# SDA381V8_B0.net
KiCad netlist of a schematic drawn in EAGLE
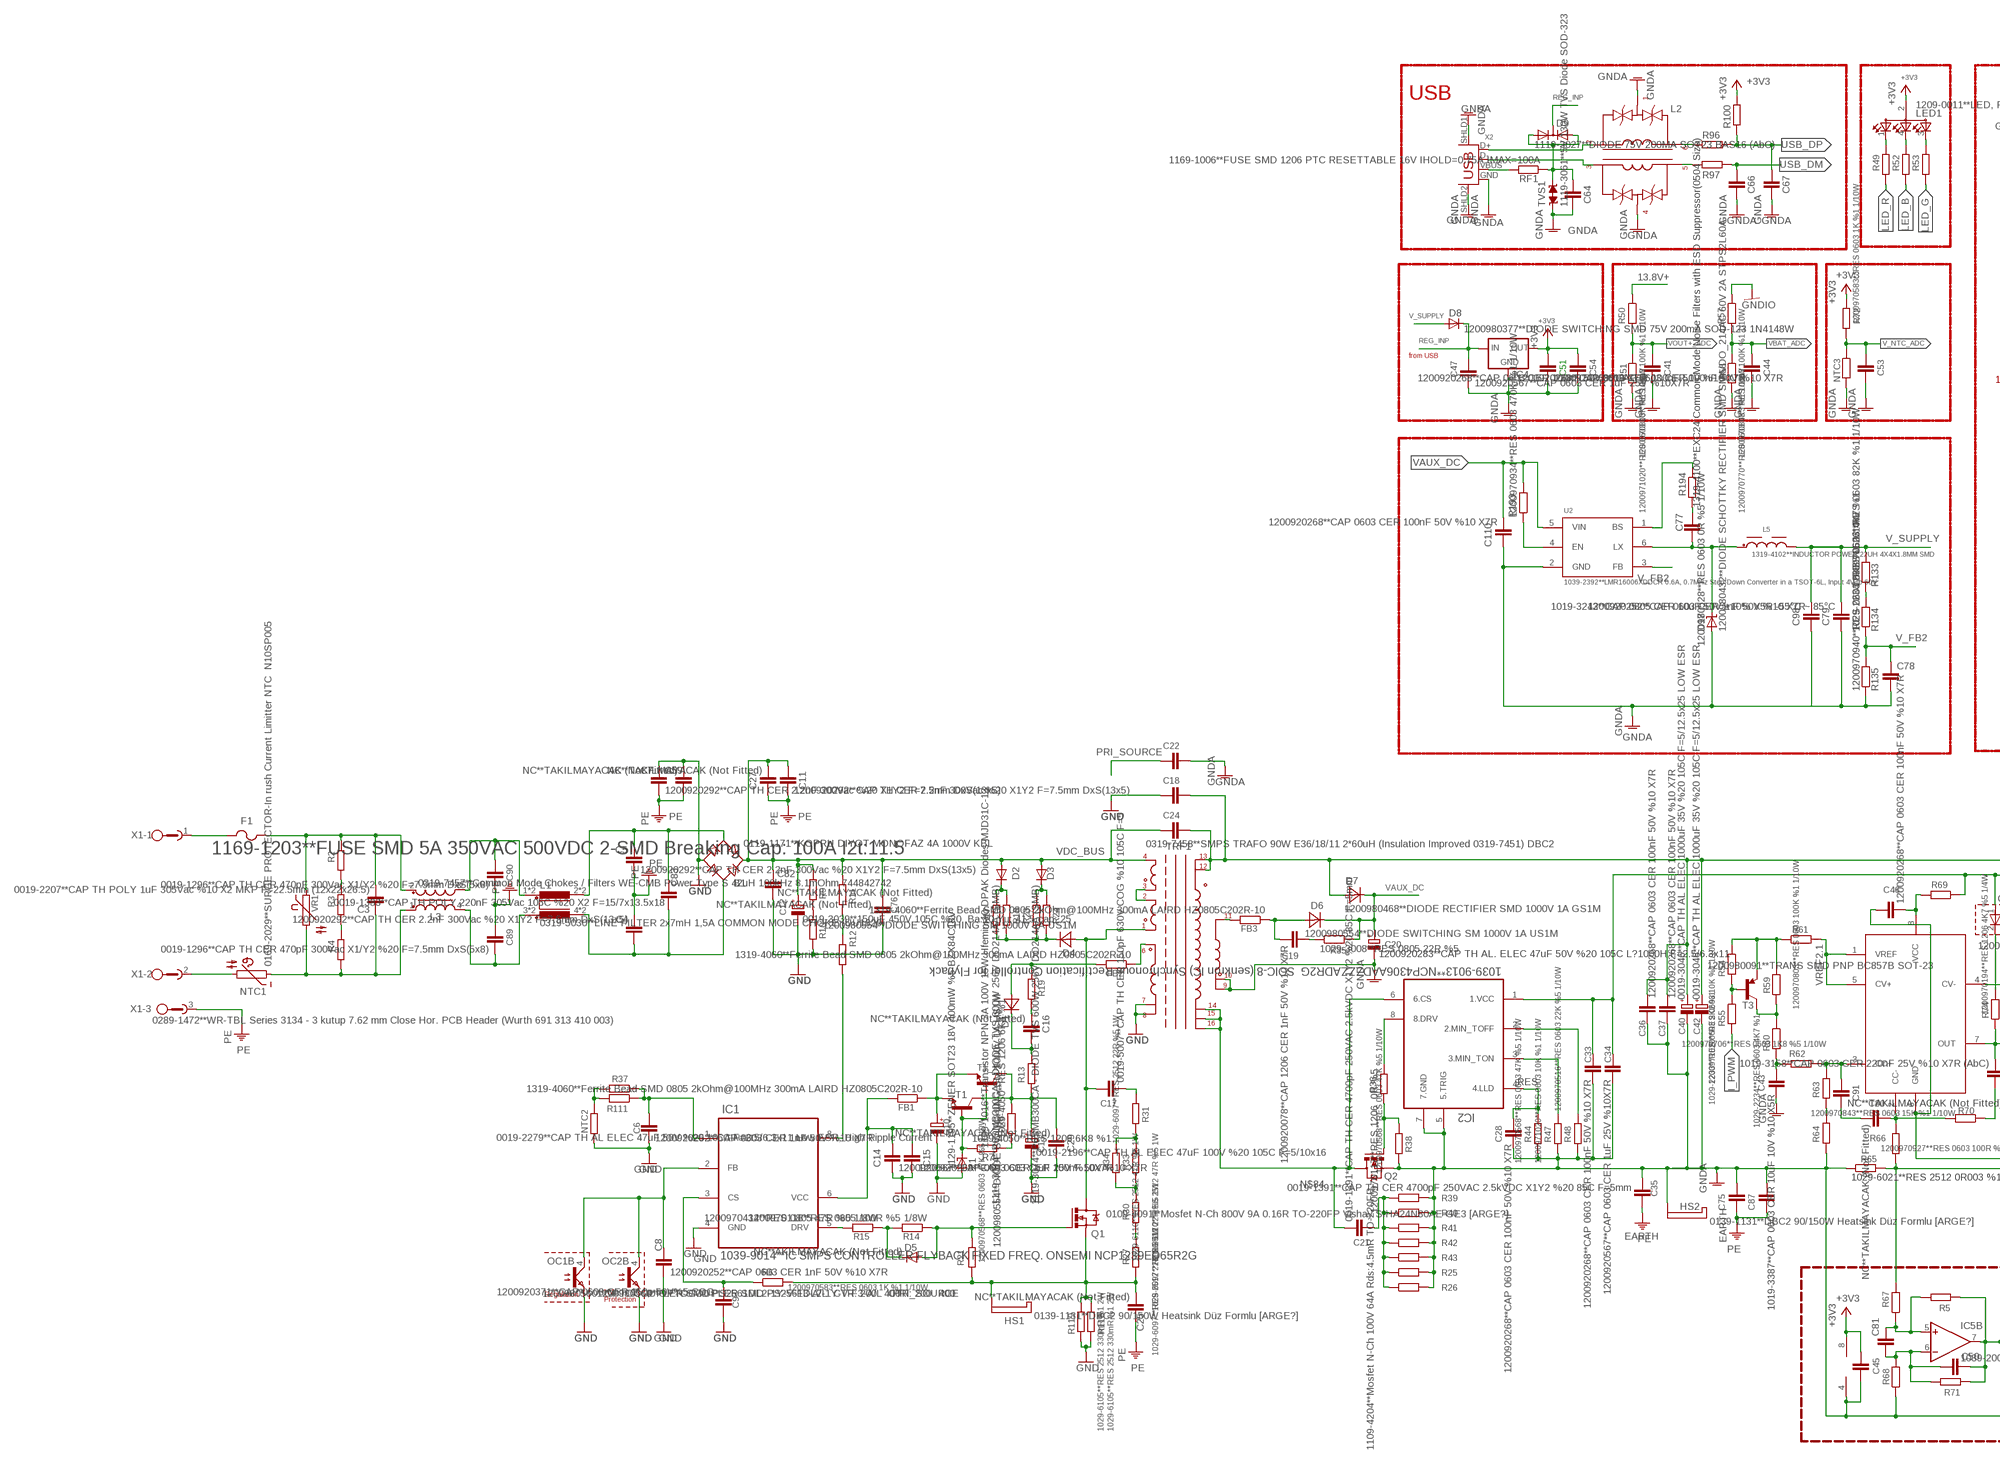
[diagram p0: schematic, sheet 1, part 1 of 2]
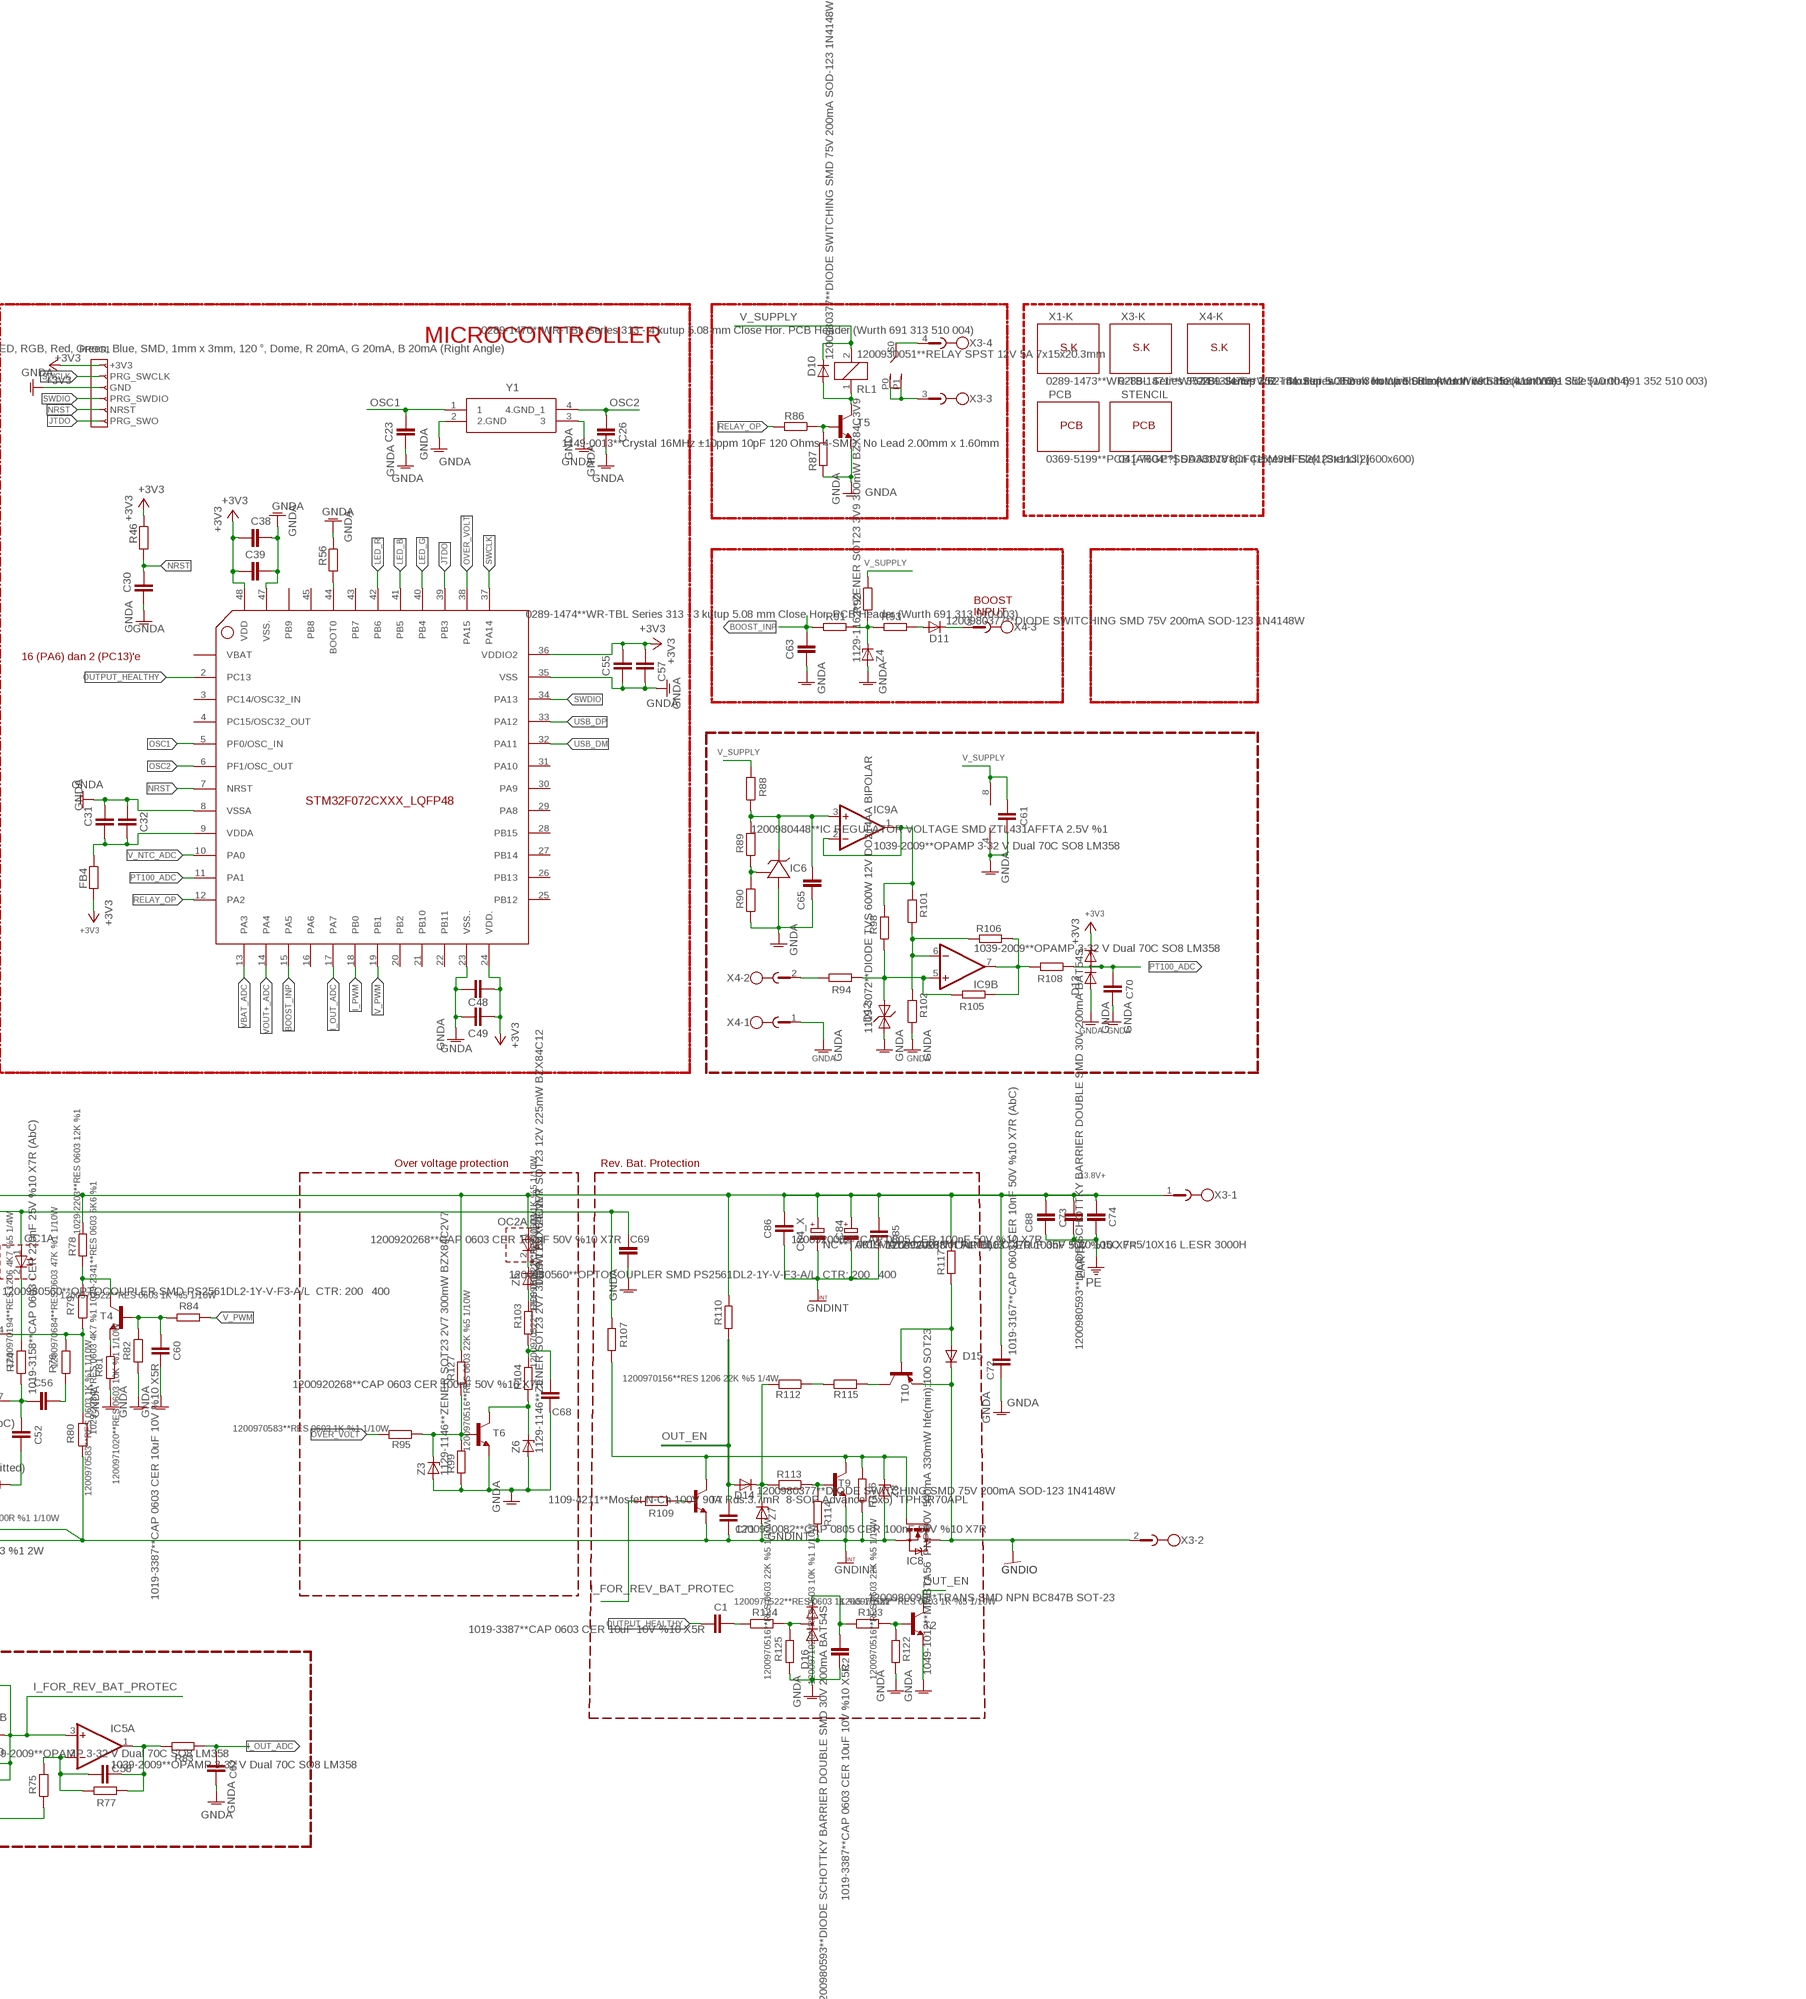
[diagram p1: schematic, sheet 1, part 2 of 2]

(export (version "E")
  (design (tool "Eeschema 10.0.6"))
  (components
    (comp (ref "B1")
      (value "0119-1171**KOPRU DIYOT MONOFAZ 4A 1000V KBL")
      (footprint "eagle-import:DıODE_BRIDGE_8A_DIK")
      (libsource (lib "eagle-import") (part "DıODE_BRIDGE_8A_DIK"))
    )
    (comp (ref "C1")
      (value "1019-3387**CAP 0603 CER 10uF 10V %10 X5R")
      (footprint "eagle-import:C0603_ENKO")
      (libsource (lib "eagle-import") (part "C-EUC0603E"))
    )
    (comp (ref "C2")
      (value "1019-3387**CAP 0603 CER 10uF 10V %10 X5R")
      (footprint "eagle-import:C0603_ENKO")
      (libsource (lib "eagle-import") (part "C-EUC0603E"))
    )
    (comp (ref "C3")
      (value "0019-2207**CAP TH POLY 1uF 305Vac %10 X2 MKP F=22.5mm (12x22x26.5)")
      (footprint "eagle-import:C275-113X316_&_C150-072X183_&_C225-113X268")
      (libsource (lib "eagle-import") (part "C275-113X316_&_C150-072X183_&_C225-113X268"))
    )
    (comp (ref "C4")
      (value "1200920292**CAP TH CER 2.2nF 300Vac %20 X1Y2 F=7.5mm DxS(13x5)")
      (footprint "eagle-import:C075-042X103")
      (libsource (lib "eagle-import") (part "C-EU075-042X103"))
    )
    (comp (ref "C5")
      (value "1200920292**CAP TH CER 2.2nF 300Vac %20 X1Y2 F=7.5mm DxS(13x5)")
      (footprint "eagle-import:C075-042X103")
      (libsource (lib "eagle-import") (part "C-EU075-042X103"))
    )
    (comp (ref "C6")
      (value "1200920252**CAP 0603 CER 1nF 50V %10 X7R")
      (footprint "eagle-import:C0603_ENKO")
      (libsource (lib "eagle-import") (part "C-EUC0603E"))
    )
    (comp (ref "C7")
      (value "1200920292**CAP TH CER 2.2nF 300Vac %20 X1Y2 F=7.5mm DxS(13x5)")
      (footprint "eagle-import:C075-042X103")
      (libsource (lib "eagle-import") (part "C-EU075-042X103"))
    )
    (comp (ref "C8")
      (value "1200920252**CAP 0603 CER 1nF 50V %10 X7R")
      (footprint "eagle-import:C0603_ENKO")
      (libsource (lib "eagle-import") (part "C-EUC0603E"))
    )
    (comp (ref "C9")
      (value "1200920371**CAP 0603 CER 150p 50V%5 COG")
      (footprint "eagle-import:C0603_ENKO")
      (libsource (lib "eagle-import") (part "C-EUC0603E"))
    )
    (comp (ref "C10")
      (value "0019-2279**CAP TH AL ELEC 47uF 50V %20 105C F=2.5/6.3x11 Low ESR, High Ripple Current")
      (footprint "eagle-import:E2,5-7")
      (libsource (lib "eagle-import") (part "CPOL-EUE2.5-7"))
    )
    (comp (ref "C11")
      (value "1200920292**CAP TH CER 2.2nF 300Vac %20 X1Y2 F=7.5mm DxS(13x5)")
      (footprint "eagle-import:C075-042X103")
      (libsource (lib "eagle-import") (part "C-EU075-042X103"))
    )
    (comp (ref "C12")
      (value "0019-3039**150uF 450V 105C %20 Ba:10 Yu: 41,5 çap: 25")
      (footprint "eagle-import:EB25D")
      (libsource (lib "eagle-import") (part "CPOL-EUE10-25"))
    )
    (comp (ref "C13")
      (value "0019-2196**CAP TH AL ELEC 47uF 100V %20 105C F=5/10x16")
      (footprint "eagle-import:E5-10,5")
      (libsource (lib "eagle-import") (part "CPOL-EUE5-10.5"))
    )
    (comp (ref "C14")
      (value "1200920567**CAP 0603 CER 1uF 25V %10X7R")
      (footprint "eagle-import:C0603_ENKO")
      (libsource (lib "eagle-import") (part "C-EUC0603E"))
    )
    (comp (ref "C15")
      (value "1200920268**CAP 0603 CER 100nF 50V %10 X7R")
      (footprint "eagle-import:C0603_ENKO")
      (libsource (lib "eagle-import") (part "C-EUC0603E"))
    )
    (comp (ref "C16")
      (value "NC**TAKILMAYACAK (Not Fitted)")
      (footprint "eagle-import:C1206_ENKO")
      (libsource (lib "eagle-import") (part "C-EUC1206E"))
    )
    (comp (ref "C17")
      (value "0019-5007**CAP TH CER 150pF 630V COG %10 105C F=5")
      (footprint "eagle-import:C075-32X103_C050-035X75")
      (libsource (lib "eagle-import") (part "C075-32X103/C050-035X75"))
    )
    (comp (ref "C18")
      (value "0019-1298**CAP TH CER 1nF 500Vac X1/Y1 %20 F=10mm DxS(5x9)")
      (footprint "eagle-import:C075-32X103_DEIF")
      (libsource (lib "eagle-import") (part "C075-32X103_DEIF"))
    )
    (comp (ref "C19")
      (value "1200920078**CAP 1206 CER 1nF 50V %10 X7R")
      (footprint "eagle-import:C1206_ENKO")
      (libsource (lib "eagle-import") (part "C-EUC1206E"))
    )
    (comp (ref "C20")
      (value "1200920283**CAP TH AL. ELEC 47uF 50V %20 105C L?1000H F=2.5/6.3x11")
      (footprint "eagle-import:E2,5-7")
      (libsource (lib "eagle-import") (part "CPOL-EUE2.5-7"))
    )
    (comp (ref "C21")
      (value "0019-1391**CAP TH CER 4700pF 250VAC 2.5kVDC X1Y2 %20 85C F=5mm")
      (footprint "eagle-import:C075-32X103_C050-035X75")
      (libsource (lib "eagle-import") (part "C075-32X103/C050-035X75"))
    )
    (comp (ref "C22")
      (value "0019-1298**CAP TH CER 1nF 500Vac X1/Y1 %20 F=10mm DxS(5x9)")
      (footprint "eagle-import:C075-32X103_DEIF")
      (libsource (lib "eagle-import") (part "C075-32X103_DEIF"))
    )
    (comp (ref "C23")
      (value "1019-3352**CAP 0603 CER 22pF 50V %5 NPO")
      (footprint "eagle-import:C0603_ENKO")
      (libsource (lib "eagle-import") (part "C-EUC0603E"))
    )
    (comp (ref "C24")
      (value "0019-1299**CAP TH CER 2.2nF 500Vac X1/Y1 %20 F=10mm DxS(5x12)")
      (footprint "eagle-import:C075-32X103_DEIF")
      (libsource (lib "eagle-import") (part "C075-32X103_DEIF"))
    )
    (comp (ref "C25")
      (value "NC**TAKILMAYACAK (Not Fitted)")
      (footprint "eagle-import:C50-035X75")
      (libsource (lib "eagle-import") (part "C50-035X75"))
    )
    (comp (ref "C26")
      (value "1019-3352**CAP 0603 CER 22pF 50V %5 NPO")
      (footprint "eagle-import:C0603_ENKO")
      (libsource (lib "eagle-import") (part "C-EUC0603E"))
    )
    (comp (ref "C27")
      (value "NC**TAKILMAYACAK (Not Fitted)")
      (footprint "eagle-import:C50-035X75")
      (libsource (lib "eagle-import") (part "C50-035X75"))
    )
    (comp (ref "C28")
      (value "1200920268**CAP 0603 CER 100nF 50V %10 X7R")
      (footprint "eagle-import:C0603_ENKO")
      (libsource (lib "eagle-import") (part "C-EUC0603E"))
    )
    (comp (ref "C29")
      (value "NC**TAKILMAYACAK (Not Fitted)")
      (footprint "eagle-import:C1206_ENKO")
      (libsource (lib "eagle-import") (part "C-EUC1206E"))
    )
    (comp (ref "C30")
      (value "1200920268**CAP 0603 CER 100nF 50V %10 X7R")
      (footprint "eagle-import:C0603_ENKO")
      (libsource (lib "eagle-import") (part "C-EUC0603E"))
    )
    (comp (ref "C31")
      (value "1200920268**CAP 0603 CER 100nF 50V %10 X7R")
      (footprint "eagle-import:C0603_ENKO")
      (libsource (lib "eagle-import") (part "C-EUC0603E"))
    )
    (comp (ref "C32")
      (value "1019-3167**CAP 0603 CER 10nF 50V %10 X7R (AbC)")
      (footprint "eagle-import:C0603_ENKO")
      (libsource (lib "eagle-import") (part "C-EUC0603E"))
    )
    (comp (ref "C33")
      (value "1200920268**CAP 0603 CER 100nF 50V %10 X7R")
      (footprint "eagle-import:C0603_ENKO")
      (libsource (lib "eagle-import") (part "C-EUC0603E"))
    )
    (comp (ref "C34")
      (value "1200920567**CAP 0603 CER 1uF 25V %10X7R")
      (footprint "eagle-import:C0603_ENKO")
      (libsource (lib "eagle-import") (part "C-EUC0603E"))
    )
    (comp (ref "C35")
      (value "0019-1391**CAP TH CER 4700pF 250VAC 2.5kVDC X1Y2 %20 85C F=5mm")
      (footprint "eagle-import:C050-045X075")
      (libsource (lib "eagle-import") (part "C-EU050-045X075"))
    )
    (comp (ref "C36")
      (value "1200920268**CAP 0603 CER 100nF 50V %10 X7R")
      (footprint "eagle-import:C0603_ENKO")
      (libsource (lib "eagle-import") (part "C-EUC0603E"))
    )
    (comp (ref "C37")
      (value "1200920268**CAP 0603 CER 100nF 50V %10 X7R")
      (footprint "eagle-import:C0603_ENKO")
      (libsource (lib "eagle-import") (part "C-EUC0603E"))
    )
    (comp (ref "C38")
      (value "1200920268**CAP 0603 CER 100nF 50V %10 X7R")
      (footprint "eagle-import:C0603_ENKO")
      (libsource (lib "eagle-import") (part "C-EUC0603E"))
    )
    (comp (ref "C39")
      (value "1019-3167**CAP 0603 CER 10nF 50V %10 X7R (AbC)")
      (footprint "eagle-import:C0603_ENKO")
      (libsource (lib "eagle-import") (part "C-EUC0603E"))
    )
    (comp (ref "C40")
      (value "0019-3046**CAP TH AL ELEC 1000uF 35V %20 105C F=5/12.5x25 LOW ESR")
      (footprint "eagle-import:E5-13_E7,5-16")
      (libsource (lib "eagle-import") (part "E5-13/E7,5-16"))
    )
    (comp (ref "C41")
      (value "1200920268**CAP 0603 CER 100nF 50V %10 X7R")
      (footprint "eagle-import:C0603_ENKO")
      (libsource (lib "eagle-import") (part "C-EUC0603E"))
    )
    (comp (ref "C42")
      (value "0019-3046**CAP TH AL ELEC 1000uF 35V %20 105C F=5/12.5x25 LOW ESR")
      (footprint "eagle-import:E5-13")
      (libsource (lib "eagle-import") (part "CPOL-EUE5-13"))
    )
    (comp (ref "C43")
      (value "1019-3387**CAP 0603 CER 10uF 10V %10 X5R")
      (footprint "eagle-import:C0603_ENKO")
      (libsource (lib "eagle-import") (part "C-EUC0603E"))
    )
    (comp (ref "C44")
      (value "1200920268**CAP 0603 CER 100nF 50V %10 X7R")
      (footprint "eagle-import:C0603_ENKO")
      (libsource (lib "eagle-import") (part "C-EUC0603E"))
    )
    (comp (ref "C45")
      (value "1200920268**CAP 0603 CER 100nF 50V %10 X7R")
      (footprint "eagle-import:C0603_ENKO")
      (libsource (lib "eagle-import") (part "C-EUC0603E"))
    )
    (comp (ref "C46")
      (value "1200920268**CAP 0603 CER 100nF 50V %10 X7R")
      (footprint "eagle-import:C0603_ENKO")
      (libsource (lib "eagle-import") (part "C-EUC0603E"))
    )
    (comp (ref "C47")
      (value "1200920567**CAP 0603 CER 1uF 25V %10X7R")
      (footprint "eagle-import:C0603_ENKO")
      (libsource (lib "eagle-import") (part "C-EUC0603E"))
    )
    (comp (ref "C48")
      (value "1019-3167**CAP 0603 CER 10nF 50V %10 X7R (AbC)")
      (footprint "eagle-import:C0603_ENKO")
      (libsource (lib "eagle-import") (part "C-EUC0603E"))
    )
    (comp (ref "C49")
      (value "1200920268**CAP 0603 CER 100nF 50V %10 X7R")
      (footprint "eagle-import:C0603_ENKO")
      (libsource (lib "eagle-import") (part "C-EUC0603E"))
    )
    (comp (ref "C50")
      (value "NC**TAKILMAYACAK (Not Fitted)")
      (footprint "eagle-import:C0603_ENKO")
      (libsource (lib "eagle-import") (part "C-EUC0603E"))
    )
    (comp (ref "C51")
      (value "1200920268**CAP 0603 CER 100nF 50V %10 X7R")
      (footprint "eagle-import:C0603_ENKO")
      (libsource (lib "eagle-import") (part "C-EUC0603E"))
    )
    (comp (ref "C52")
      (value "1019-3158**CAP 0603 CER 220nF 25V %10 X7R (AbC)")
      (footprint "eagle-import:C0603_ENKO")
      (libsource (lib "eagle-import") (part "C-EUC0603E"))
    )
    (comp (ref "C53")
      (value "1200920268**CAP 0603 CER 100nF 50V %10 X7R")
      (footprint "eagle-import:C0603_ENKO")
      (libsource (lib "eagle-import") (part "C-EUC0603E"))
    )
    (comp (ref "C54")
      (value "1019-3301**CAP 0805 47uF 6.3V %20 X5R")
      (footprint "eagle-import:C0805_ENKO")
      (libsource (lib "eagle-import") (part "C-EUC0805E"))
    )
    (comp (ref "C55")
      (value "1019-3167**CAP 0603 CER 10nF 50V %10 X7R (AbC)")
      (footprint "eagle-import:C0603_ENKO")
      (libsource (lib "eagle-import") (part "C-EUC0603E"))
    )
    (comp (ref "C56")
      (value "1019-3158**CAP 0603 CER 220nF 25V %10 X7R (AbC)")
      (footprint "eagle-import:C0603_ENKO")
      (libsource (lib "eagle-import") (part "C-EUC0603E"))
    )
    (comp (ref "C57")
      (value "1200920268**CAP 0603 CER 100nF 50V %10 X7R")
      (footprint "eagle-import:C0603_ENKO")
      (libsource (lib "eagle-import") (part "C-EUC0603E"))
    )
    (comp (ref "C58")
      (value "1200920371**CAP 0603 CER 150p 50V%5 COG")
      (footprint "eagle-import:C0603_ENKO")
      (libsource (lib "eagle-import") (part "C-EUC0603E"))
    )
    (comp (ref "C59")
      (value "NC**TAKILMAYACAK (Not Fitted)")
      (footprint "eagle-import:C50-035X75")
      (libsource (lib "eagle-import") (part "C50-035X75"))
    )
    (comp (ref "C60")
      (value "1019-3387**CAP 0603 CER 10uF 10V %10 X5R")
      (footprint "eagle-import:C0603_ENKO")
      (libsource (lib "eagle-import") (part "C-EUC0603E"))
    )
    (comp (ref "C61")
      (value "1200920268**CAP 0603 CER 100nF 50V %10 X7R")
      (footprint "eagle-import:C0603_ENKO")
      (libsource (lib "eagle-import") (part "C-EUC0603E"))
    )
    (comp (ref "C62")
      (value "1200920268**CAP 0603 CER 100nF 50V %10 X7R")
      (footprint "eagle-import:C0603_ENKO")
      (libsource (lib "eagle-import") (part "C-EUC0603E"))
    )
    (comp (ref "C63")
      (value "1019-3167**CAP 0603 CER 10nF 50V %10 X7R (AbC)")
      (footprint "eagle-import:C0603_ENKO")
      (libsource (lib "eagle-import") (part "C-EUC0603E"))
    )
    (comp (ref "C64")
      (value "1200920268**CAP 0603 CER 100nF 50V %10 X7R")
      (footprint "eagle-import:C0603_ENKO")
      (libsource (lib "eagle-import") (part "C-EUC0603E"))
    )
    (comp (ref "C65")
      (value "1200920268**CAP 0603 CER 100nF 50V %10 X7R")
      (footprint "eagle-import:C0603_ENKO")
      (libsource (lib "eagle-import") (part "C-EUC0603E"))
    )
    (comp (ref "C66")
      (value "1019-3381**CAP 0603 CER 33pf 50V %5 NPO(COG)")
      (footprint "eagle-import:C0603_ENKO")
      (libsource (lib "eagle-import") (part "C-EUC0603E"))
    )
    (comp (ref "C67")
      (value "1019-3381**CAP 0603 CER 33pf 50V %5 NPO(COG)")
      (footprint "eagle-import:C0603_ENKO")
      (libsource (lib "eagle-import") (part "C-EUC0603E"))
    )
    (comp (ref "C68")
      (value "1200920268**CAP 0603 CER 100nF 50V %10 X7R")
      (footprint "eagle-import:C0603_ENKO")
      (libsource (lib "eagle-import") (part "C-EUC0603E"))
    )
    (comp (ref "C69")
      (value "1200920268**CAP 0603 CER 100nF 50V %10 X7R")
      (footprint "eagle-import:C0603_ENKO")
      (libsource (lib "eagle-import") (part "C-EUC0603E"))
    )
    (comp (ref "C70")
      (value "1200920268**CAP 0603 CER 100nF 50V %10 X7R")
      (footprint "eagle-import:C0603_ENKO")
      (libsource (lib "eagle-import") (part "C-EUC0603E"))
    )
    (comp (ref "C71")
      (value "1200920082**CAP 0805 CER 100nF 50V %10 X7R")
      (footprint "eagle-import:C0805_ENKO")
      (libsource (lib "eagle-import") (part "C-EUC0805E"))
    )
    (comp (ref "C72")
      (value "1019-3167**CAP 0603 CER 10nF 50V %10 X7R (AbC)")
      (footprint "eagle-import:C0603_ENKO")
      (libsource (lib "eagle-import") (part "C-EUC0603E"))
    )
    (comp (ref "C73")
      (value "0019-1391**CAP TH CER 4700pF 250VAC 2.5kVDC X1Y2 %20 85C F=5mm")
      (footprint "eagle-import:C050-035X075")
      (libsource (lib "eagle-import") (part "C-EU050-035X075"))
    )
    (comp (ref "C74")
      (value "0019-1391**CAP TH CER 4700pF 250VAC 2.5kVDC X1Y2 %20 85C F=5mm")
      (footprint "eagle-import:C075-32X103_DEIF")
      (libsource (lib "eagle-import") (part "C075-32X103_DEIF"))
    )
    (comp (ref "C75")
      (value "0019-1391**CAP TH CER 4700pF 250VAC 2.5kVDC X1Y2 %20 85C F=5mm")
      (footprint "eagle-import:C075-32X103_DEIF")
      (libsource (lib "eagle-import") (part "C075-32X103_DEIF"))
    )
    (comp (ref "C76")
      (value "NC**TAKILMAYACAK (Not Fitted)")
      (footprint "eagle-import:C065-052X106")
      (libsource (lib "eagle-import") (part "C065-052X106"))
    )
    (comp (ref "C77")
      (value "1200920268**CAP 0603 CER 100nF 50V %10 X7R")
      (footprint "eagle-import:C0603_ENKO")
      (libsource (lib "eagle-import") (part "C-EUC0603E"))
    )
    (comp (ref "C78")
      (value "1019-3352**CAP 0603 CER 22pF 50V %5 NPO")
      (footprint "eagle-import:C0603_ENKO")
      (libsource (lib "eagle-import") (part "C-EUC0603E"))
    )
    (comp (ref "C79")
      (value "1019-3243**CAP 0805 CER 10uF 50V ±10% X5R -55°C ~ 85°C")
      (footprint "eagle-import:C0805_ENKO")
      (libsource (lib "eagle-import") (part "C-EUC0805E"))
    )
    (comp (ref "C80")
      (value "NC**TAKILMAYACAK (Not Fitted)")
      (footprint "eagle-import:C0603_ENKO")
      (libsource (lib "eagle-import") (part "C-EUC0603E"))
    )
    (comp (ref "C81")
      (value "NC**TAKILMAYACAK (Not Fitted)")
      (footprint "eagle-import:C0603_ENKO")
      (libsource (lib "eagle-import") (part "C-EUC0603E"))
    )
    (comp (ref "C82")
      (value "NC**TAKILMAYACAK (Not Fitted)")
      (footprint "eagle-import:C150-091X182")
      (libsource (lib "eagle-import") (part "C-EU150-091X182"))
    )
    (comp (ref "C83")
      (value "0019-1383**CAP TH POLY 220nF 305Vac 105C %20 X2 F=15/7x13.5x18")
      (footprint "eagle-import:C150-091X182_C225-108X268")
      (libsource (lib "eagle-import") (part "C150-091X182_C225-108X268"))
    )
    (comp (ref "C84")
      (value "0019-7012**CAP TH AL. ELEC 470uF 35V %20 105C F=5/10X16 L.ESR 3000H")
      (footprint "eagle-import:E5-10,5")
      (libsource (lib "eagle-import") (part "CPOL-EUE5-10.5"))
    )
    (comp (ref "C84_X")
      (value "NC**TAKILMAYACAK (Not Fitted)")
      (footprint "eagle-import:E2,5-7")
      (libsource (lib "eagle-import") (part "CPOL-EUE2.5-7"))
    )
    (comp (ref "C85")
      (value "1200920268**CAP 0603 CER 100nF 50V %10 X7R")
      (footprint "eagle-import:C0603_ENKO")
      (libsource (lib "eagle-import") (part "C-EUC0603E"))
    )
    (comp (ref "C86")
      (value "1200920082**CAP 0805 CER 100nF 50V %10 X7R")
      (footprint "eagle-import:C0805_ENKO")
      (libsource (lib "eagle-import") (part "C-EUC0805E"))
    )
    (comp (ref "C87")
      (value "0019-3044**CAP TH CER 1nF 400VAC X1 %20 85C F=5 veya F=7.5 D=6.5")
      (footprint "eagle-import:C075-32X103_DEIF")
      (libsource (lib "eagle-import") (part "C075-32X103_DEIF"))
    )
    (comp (ref "C88")
      (value "0019-3044**CAP TH CER 1nF 400VAC X1 %20 85C F=5 veya F=7.5 D=6.5")
      (footprint "eagle-import:C075-32X103_DEIF")
      (libsource (lib "eagle-import") (part "C075-32X103_DEIF"))
    )
    (comp (ref "C89")
      (value "0019-1296**CAP TH CER 470pF 300Vac X1/Y2 %20 F=7.5mm DxS(5x8)")
      (footprint "eagle-import:C075-32X103_C050-035X75")
      (libsource (lib "eagle-import") (part "C075-32X103/C050-035X75"))
    )
    (comp (ref "C90")
      (value "0019-1296**CAP TH CER 470pF 300Vac X1/Y2 %20 F=7.5mm DxS(5x8)")
      (footprint "eagle-import:C075-32X103_C050-035X75")
      (libsource (lib "eagle-import") (part "C075-32X103/C050-035X75"))
    )
    (comp (ref "C91")
      (value "NC**TAKILMAYACAK (Not Fitted)")
      (footprint "eagle-import:C0603_ENKO")
      (libsource (lib "eagle-import") (part "C-EUC0603E"))
    )
    (comp (ref "C98")
      (value "1200920252**CAP 0603 CER 1nF 50V %10 X7R")
      (footprint "eagle-import:C0603_ENKO")
      (libsource (lib "eagle-import") (part "C-EUC0603E"))
    )
    (comp (ref "C110")
      (value "1200920268**CAP 0603 CER 100nF 50V %10 X7R")
      (footprint "eagle-import:C0603_ENKO")
      (libsource (lib "eagle-import") (part "C-EUC0603E"))
    )
    (comp (ref "D1")
      (value "1200980554**DIODE SWITCHING SM 1000V 1A US1M")
      (footprint "eagle-import:M7_DC_DIYOT")
      (libsource (lib "eagle-import") (part "M7_DC_DIYOT"))
    )
    (comp (ref "D2")
      (value "1119-3074**P6SMB300CA - DIODE TVS 600W 256V DO214AA (SMB)")
      (footprint "eagle-import:SMB")
      (libsource (lib "eagle-import") (part "DIODE-SMB"))
    )
    (comp (ref "D3")
      (value "1119-3074**P6SMB300CA - DIODE TVS 600W 256V DO214AA (SMB)")
      (footprint "eagle-import:SMB")
      (libsource (lib "eagle-import") (part "DIODE-SMB"))
    )
    (comp (ref "D4")
      (value "1200980554**DIODE SWITCHING SM 1000V 1A US1M")
      (footprint "eagle-import:M7_DC_DIYOT")
      (libsource (lib "eagle-import") (part "M7_DC_DIYOT"))
    )
    (comp (ref "D5")
      (value "NC**AKILMAYACAK (Not Fitted)")
      (footprint "eagle-import:SOD123")
      (libsource (lib "eagle-import") (part "DIODE-SOD123"))
    )
    (comp (ref "D6")
      (value "1200980554**DIODE SWITCHING SM 1000V 1A US1M")
      (footprint "eagle-import:M7_DC_DIYOT")
      (libsource (lib "eagle-import") (part "M7_DC_DIYOT"))
    )
    (comp (ref "D7")
      (value "1200980468**DIODE RECTIFIER SMD 1000V 1A GS1M")
      (footprint "eagle-import:M7_DC_DIYOT")
      (libsource (lib "eagle-import") (part "M7_DC_DIYOT"))
    )
    (comp (ref "D8")
      (value "1200980377**DIODE SWITCHING SMD 75V 200mA SOD-123 1N4148W")
      (footprint "eagle-import:SOD123")
      (libsource (lib "eagle-import") (part "DIODE-SOD123"))
    )
    (comp (ref "D9")
      (value "1119-3027**DIODE 75V 200MA SOT23 BAS16 (AbC)")
      (footprint "eagle-import:SOT23")
      (libsource (lib "eagle-import") (part "DIODE-2AC|CASOT23"))
    )
    (comp (ref "D10")
      (value "1200980377**DIODE SWITCHING SMD 75V 200mA SOD-123 1N4148W")
      (footprint "eagle-import:SOD123")
      (libsource (lib "eagle-import") (part "DIODE-SOD123"))
    )
    (comp (ref "D11")
      (value "1200980377**DIODE SWITCHING SMD 75V 200mA SOD-123 1N4148W")
      (footprint "eagle-import:SOD123")
      (libsource (lib "eagle-import") (part "DIODE-SOD123"))
    )
    (comp (ref "D12")
      (value "1119-3072**DIODE TVS 600W 12V DO214AA BIPOLAR")
      (footprint "eagle-import:TRANSIL_SMB")
      (libsource (lib "eagle-import") (part "TRANSIL_SMB"))
    )
    (comp (ref "D13")
      (value "1200980593**DIODE SCHOTTKY BARRIER DOUBLE SMD 30V 200mA BAT54S")
      (footprint "eagle-import:SOT23")
      (libsource (lib "eagle-import") (part "BAV199"))
    )
    (comp (ref "D14")
      (value "1200980377**DIODE SWITCHING SMD 75V 200mA SOD-123 1N4148W")
      (footprint "eagle-import:SOD123")
      (libsource (lib "eagle-import") (part "DIODE-SOD123"))
    )
    (comp (ref "D15")
      (value "1200980377**DIODE SWITCHING SMD 75V 200mA SOD-123 1N4148W")
      (footprint "eagle-import:SOD123")
      (libsource (lib "eagle-import") (part "DIODE-SOD123"))
    )
    (comp (ref "D16")
      (value "1200980593**DIODE SCHOTTKY BARRIER DOUBLE SMD 30V 200mA BAT54S")
      (footprint "eagle-import:SOT23")
      (libsource (lib "eagle-import") (part "BAV199"))
    )
    (comp (ref "D18")
      (value "1200980432**DIODE SCHOTTKY RECTIFIER SMD SMA/DO_214AC 60V 2A STPS2L60A")
      (footprint "eagle-import:SMA")
      (libsource (lib "eagle-import") (part "SD-SMA"))
    )
    (comp (ref "F1")
      (value "1169-1203**FUSE SMD 5A 350VAC 500VDC 2-SMD Breaking Cap: 100A I2t:11.5")
      (footprint "eagle-import:FUSE_1350HV_EAT")
      (fields
        (field (name "MANUFACTURER_PART_NUMBER") "TR-1350HV5-R")
        (field (name "COPYRIGHT") "Copyright (C) 2025 Ultra Librarian. All rights reserved.")
      )
      (libsource (lib "eagle-import") (part "TR-1350HV5-RFUSE_1350HV_EAT"))
    )
    (comp (ref "FB1")
      (value "1319-4060**Ferrite Bead SMD 0805 2kOhm@100MHz 300mA LAIRD HZ0805C202R-10")
      (footprint "eagle-import:R0805_ENKO")
      (libsource (lib "eagle-import") (part "R-EU_R0805E"))
    )
    (comp (ref "FB2")
      (value "1319-4060**Ferrite Bead SMD 0805 2kOhm@100MHz 300mA LAIRD HZ0805C202R-10")
      (footprint "eagle-import:R0805_ENKO")
      (libsource (lib "eagle-import") (part "R-EU_R0805E"))
    )
    (comp (ref "FB3")
      (value "1319-4060**Ferrite Bead SMD 0805 2kOhm@100MHz 300mA LAIRD HZ0805C202R-10")
      (footprint "eagle-import:R0805_ENKO")
      (libsource (lib "eagle-import") (part "R-EU_R0805E"))
    )
    (comp (ref "FB4")
      (value "1319-4060**Ferrite Bead SMD 0805 2kOhm@100MHz 300mA LAIRD HZ0805C202R-10")
      (footprint "eagle-import:R0805_ENKO")
      (libsource (lib "eagle-import") (part "R-EU_R0805E"))
    )
    (comp (ref "HS1")
      (value "0139-1131**DBC2 90/150W Heatsink Düz Formlu [ARGE?]")
      (footprint "eagle-import:DEIF_SOGUTUCU_2")
      (libsource (lib "eagle-import") (part "DEIF_SOGUTUCU_2"))
    )
    (comp (ref "HS2")
      (value "0139-1131**DBC2 90/150W Heatsink Düz Formlu [ARGE?]")
      (footprint "eagle-import:DEIF_SOGUTUCU_2")
      (libsource (lib "eagle-import") (part "DEIF_SOGUTUCU_2"))
    )
    (comp (ref "IC1")
      (value "1039-9014**IC SMPS CONTROLLER FLYBACK FIXED FREQ. ONSEMI NCP1239ED65R2G")
      (footprint "eagle-import:NCP1239_SMPS_IC")
      (libsource (lib "eagle-import") (part "NCP1239_SMPS_IC"))
    )
    (comp (ref "IC2")
      (value "1039-9013**NCP4306AADZZZADR2G SOIC-8 (senkron IC) Synchronous Rectification Controller for Flyback")
      (footprint "eagle-import:NCP4306")
      (libsource (lib "eagle-import") (part "NCP4306"))
    )
    (comp (ref "IC3")
      (value "1039-2224**TSM1011ID SO-8 Constant Voltage and Constant Current Controller")
      (footprint "eagle-import:SO-8")
      (libsource (lib "eagle-import") (part "TSM1011"))
    )
    (comp (ref "IC4")
      (value "1039-3003**Voltage Regulator SOT-89 3.3V Diodes AP2204RA-3.3TRG1")
      (footprint "eagle-import:SOT89")
      (libsource (lib "eagle-import") (part "S-812XSGUP"))
    )
    (comp (ref "IC5")
      (value "1039-2009**OPAMP 3-32 V Dual 70C SO8 LM358")
      (footprint "eagle-import:SO08")
      (libsource (lib "eagle-import") (part "LM358D"))
    )
    (comp (ref "IC6")
      (value "1200980448**IC REGULATOR VOLTAGE SMD ZTL431AFFTA 2.5V %1")
      (footprint "eagle-import:TL431_SOT23F")
      (libsource (lib "eagle-import") (part "TL431_SOT23F"))
    )
    (comp (ref "IC8")
      (value "1109-4211**Mosfet N-Ch 100V 90A Rds:3.7mR 8-SOP Advance (5x5) TPH3R70APL")
      (footprint "eagle-import:TPH6R30ANL")
      (libsource (lib "eagle-import") (part "TPH6R30ANL"))
    )
    (comp (ref "IC9")
      (value "1039-2009**OPAMP 3-32 V Dual 70C SO8 LM358")
      (footprint "eagle-import:SO08")
      (libsource (lib "eagle-import") (part "LM358D"))
    )
    (comp (ref "L1")
      (value "0319-5030**LINE FILTER 2x7mH 1,5A COMMON MODE CHOKE (UU1620)")
      (footprint "eagle-import:UU1620_&_FWCMET24V")
      (libsource (lib "eagle-import") (part "UU1620_&_FWCMET24V"))
    )
    (comp (ref "L2")
      (value "1319-4100**EXC24 Common Mode Noise Filters with ESD Suppressor(0504 Size)")
      (footprint "eagle-import:EXC24CS_COMMON_MODE")
      (libsource (lib "eagle-import") (part "EXC24CS_COMMON_MODE"))
    )
    (comp (ref "L3")
      (value "0319-7457**Common Mode Chokes / Filters WE-CMB Power Type S 42uH 100kHz 8.1mOhm 744842742")
      (footprint "eagle-import:WE-CMB_NIZN_S")
      (libsource (lib "eagle-import") (part "WE-CMB_NIZN_S_744842742"))
    )
    (comp (ref "L5")
      (value "1319-4102**INDUCTOR POWER 22UH 4X4X1.8MM SMD")
      (footprint "eagle-import:INDUCTOR-NR4018")
      (libsource (lib "eagle-import") (part "INDUCTOR-NR4018"))
    )
    (comp (ref "LED1")
      (value "1209-0011**LED, RGB, Red, Green, Blue, SMD, 1mm x 3mm, 120 °, Dome, R 20mA, G 20mA, B 20mA (Right Angle)")
      (footprint "eagle-import:KPFA-3010RGBC-11")
      (libsource (lib "eagle-import") (part "KPFA-3010RGBC-11"))
    )
    (comp (ref "NTC1")
      (value "0169-2029**SURGE PROTECTOR-In rush Current Limitter NTC N10SP005")
      (footprint "eagle-import:NTC_15R_2A_&_N15SP005-5")
      (libsource (lib "eagle-import") (part "NTC_15R_2A_&_N15SP005-5"))
    )
    (comp (ref "NTC2")
      (value "1200970116**RES 0805 0R %5")
      (footprint "eagle-import:R0805_ENKO")
      (libsource (lib "eagle-import") (part "R-EU_R0805E"))
    )
    (comp (ref "NTC3")
      (value "1169-1001**TSM2A103F3951RZ THINKING 0805 10K NTC 125C")
      (footprint "eagle-import:R0805_ENKO")
      (libsource (lib "eagle-import") (part "R-EU_R0805E"))
    )
    (comp (ref "OC1")
      (value "1200980560**OPTOCOUPLER SMD PS2561DL2-1Y-V-F3-A/L  CTR: 200˜400")
      (footprint "eagle-import:PS2561DL2-1_OPTO1")
      (libsource (lib "eagle-import") (part "PS2561DL2-1_OPTO1"))
    )
    (comp (ref "OC2")
      (value "1200980560**OPTOCOUPLER SMD PS2561DL2-1Y-V-F3-A/L  CTR: 200˜400")
      (footprint "eagle-import:PS2561DL2-1_OPTO1")
      (libsource (lib "eagle-import") (part "PS2561DL2-1_OPTO1"))
    )
    (comp (ref "PCB")
      (value "0369-5199**PCB [ARGE?] SDA381V8CF416M3HFS2(123x113.2)")
      (footprint "eagle-import:PCB")
      (libsource (lib "eagle-import") (part "PCB"))
    )
    (comp (ref "PROG1")
      (value "NC**TAKILMAYACAK (Not Fitted)")
      (footprint "eagle-import:PROG_6PIN")
      (libsource (lib "eagle-import") (part "PROG_6PIN"))
    )
    (comp (ref "Q1")
      (value "0109-4091**Mosfet N-Ch 800V 9A 0.16R TO-220FP Vishay SIHA24N80AE-GE3 [ARGE?]")
      (footprint "eagle-import:TO220BV")
      (libsource (lib "eagle-import") (part "STP5NA50"))
    )
    (comp (ref "Q2")
      (value "1109-4204**Mosfet N-Ch 100V 64A Rds:4.5mR TO-220FP")
      (footprint "eagle-import:TO220BV")
      (libsource (lib "eagle-import") (part "STP5NA50"))
    )
    (comp (ref "R2")
      (value "1200970587**RES 1206 470K %5 1/4W")
      (footprint "eagle-import:R1206_ENKO")
      (libsource (lib "eagle-import") (part "R-EU_R1206E"))
    )
    (comp (ref "R3")
      (value "1200970587**RES 1206 470K %5 1/4W")
      (footprint "eagle-import:R1206_ENKO")
      (libsource (lib "eagle-import") (part "R-EU_R1206E"))
    )
    (comp (ref "R4")
      (value "1200970587**RES 1206 470K %5 1/4W")
      (footprint "eagle-import:R1206_ENKO")
      (libsource (lib "eagle-import") (part "R-EU_R1206E"))
    )
    (comp (ref "R5")
      (value "NC**TAKILMAYACAK")
      (footprint "eagle-import:R0603_ENKO")
      (libsource (lib "eagle-import") (part "R-EU_R0603E"))
    )
    (comp (ref "R6")
      (value "1200970583**RES 0603 1K %1 1/10W")
      (footprint "eagle-import:R0603_ENKO")
      (libsource (lib "eagle-import") (part "R-EU_R0603E"))
    )
    (comp (ref "R7")
      (value "1029-4050**RES 1206 6K8 %1")
      (footprint "eagle-import:R1206_ENKO")
      (libsource (lib "eagle-import") (part "R-EU_R1206E"))
    )
    (comp (ref "R8")
      (value "1029-4050**RES 1206 6K8 %1")
      (footprint "eagle-import:R1206_ENKO")
      (libsource (lib "eagle-import") (part "R-EU_R1206E"))
    )
    (comp (ref "R9")
      (value "1200970179**RES 1206 330K %5 1/4W")
      (footprint "eagle-import:R1206_ENKO")
      (libsource (lib "eagle-import") (part "R-EU_R1206E"))
    )
    (comp (ref "R10")
      (value "1200970179**RES 1206 330K %5 1/4W")
      (footprint "eagle-import:R1206_ENKO")
      (libsource (lib "eagle-import") (part "R-EU_R1206E"))
    )
    (comp (ref "R11")
      (value "1200970154**RES 1206 2K2 %5 1/4W")
      (footprint "eagle-import:R1206_ENKO")
      (libsource (lib "eagle-import") (part "R-EU_R1206E"))
    )
    (comp (ref "R12")
      (value "1200970154**RES 1206 2K2 %5 1/4W")
      (footprint "eagle-import:R1206_ENKO")
      (libsource (lib "eagle-import") (part "R-EU_R1206E"))
    )
    (comp (ref "R13")
      (value "1029-3146**RES 1206 7R68 %1")
      (footprint "eagle-import:R1206_ENKO")
      (libsource (lib "eagle-import") (part "R-EU_R1206E"))
    )
    (comp (ref "R14")
      (value "1200970118**RES 0805 100R %5 1/8W")
      (footprint "eagle-import:R0805_ENKO")
      (libsource (lib "eagle-import") (part "R-EU_R0805E"))
    )
    (comp (ref "R15")
      (value "1200970434**RES 0805 47R %5 1/8W")
      (footprint "eagle-import:R0805_ENKO")
      (libsource (lib "eagle-import") (part "R-EU_R0805E"))
    )
    (comp (ref "R17")
      (value "1029-3146**RES 1206 7R68 %1")
      (footprint "eagle-import:R1206_ENKO")
      (libsource (lib "eagle-import") (part "R-EU_R1206E"))
    )
    (comp (ref "R18")
      (value "1029-3146**RES 1206 7R68 %1")
      (footprint "eagle-import:R1206_ENKO")
      (libsource (lib "eagle-import") (part "R-EU_R1206E"))
    )
    (comp (ref "R19")
      (value "NC**TAKILMAYACAK (Not Fitted)")
      (footprint "eagle-import:R1206_ENKO")
      (libsource (lib "eagle-import") (part "R-EU_R1206E"))
    )
    (comp (ref "R21")
      (value "1200970568**RES 0603 47K %5 1/10W")
      (footprint "eagle-import:R0603_ENKO")
      (libsource (lib "eagle-import") (part "R-EU_R0603E"))
    )
    (comp (ref "R23")
      (value "1029-3146**RES 1206 7R68 %1")
      (footprint "eagle-import:R1206_ENKO")
      (libsource (lib "eagle-import") (part "R-EU_R1206E"))
    )
    (comp (ref "R24")
      (value "1029-3146**RES 1206 7R68 %1")
      (footprint "eagle-import:R1206_ENKO")
      (libsource (lib "eagle-import") (part "R-EU_R1206E"))
    )
    (comp (ref "R25")
      (value "1200970119**RES 1206 100R %5 1/4W")
      (footprint "eagle-import:R1206_ENKO")
      (libsource (lib "eagle-import") (part "R-EU_R1206E"))
    )
    (comp (ref "R26")
      (value "1200970119**RES 1206 100R %5 1/4W")
      (footprint "eagle-import:R1206_ENKO")
      (libsource (lib "eagle-import") (part "R-EU_R1206E"))
    )
    (comp (ref "R27")
      (value "1029-6097**RES 2512 22R %5 1W")
      (footprint "eagle-import:R2512")
      (libsource (lib "eagle-import") (part "R-EU_R2512"))
    )
    (comp (ref "R30")
      (value "1029-6097**RES 2512 22R %5 1W")
      (footprint "eagle-import:R2512")
      (libsource (lib "eagle-import") (part "R-EU_R2512"))
    )
    (comp (ref "R31")
      (value "1029-6097**RES 2512 22R %5 1W")
      (footprint "eagle-import:R2512")
      (libsource (lib "eagle-import") (part "R-EU_R2512"))
    )
    (comp (ref "R33")
      (value "1029-6110**RES 2512 47R %5 1W")
      (footprint "eagle-import:R2512")
      (libsource (lib "eagle-import") (part "R-EU_R2512"))
    )
    (comp (ref "R34")
      (value "1029-6110**RES 2512 47R %5 1W")
      (footprint "eagle-import:R2512")
      (libsource (lib "eagle-import") (part "R-EU_R2512"))
    )
    (comp (ref "R35")
      (value "1029-3008**RES 0805 22R %5")
      (footprint "eagle-import:R0805_ENKO")
      (libsource (lib "eagle-import") (part "R-EU_R0805E"))
    )
    (comp (ref "R36")
      (value "1200970117**RES 1206 0R %5")
      (footprint "eagle-import:R1206_ENKO")
      (libsource (lib "eagle-import") (part "R-EU_R1206E"))
    )
    (comp (ref "R37")
      (value "1200970687**RES 0603 56K %1 1/10W")
      (footprint "eagle-import:R0603_ENKO")
      (libsource (lib "eagle-import") (part "R-EU_R0603E"))
    )
    (comp (ref "R38")
      (value "1200970568**RES 0603 47K %5 1/10W")
      (footprint "eagle-import:R0603_ENKO")
      (libsource (lib "eagle-import") (part "R-EU_R0603E"))
    )
    (comp (ref "R39")
      (value "1200970119**RES 1206 100R %5 1/4W")
      (footprint "eagle-import:R1206_ENKO")
      (libsource (lib "eagle-import") (part "R-EU_R1206E"))
    )
    (comp (ref "R40")
      (value "1200970119**RES 1206 100R %5 1/4W")
      (footprint "eagle-import:R1206_ENKO")
      (libsource (lib "eagle-import") (part "R-EU_R1206E"))
    )
    (comp (ref "R41")
      (value "1200970119**RES 1206 100R %5 1/4W")
      (footprint "eagle-import:R1206_ENKO")
      (libsource (lib "eagle-import") (part "R-EU_R1206E"))
    )
    (comp (ref "R42")
      (value "1200970119**RES 1206 100R %5 1/4W")
      (footprint "eagle-import:R1206_ENKO")
      (libsource (lib "eagle-import") (part "R-EU_R1206E"))
    )
    (comp (ref "R43")
      (value "1200970554**RES 1206 56R %1 1/4W")
      (footprint "eagle-import:R1206_ENKO")
      (libsource (lib "eagle-import") (part "R-EU_R1206E"))
    )
    (comp (ref "R44")
      (value "1200970568**RES 0603 47K %5 1/10W")
      (footprint "eagle-import:R0603_ENKO")
      (libsource (lib "eagle-import") (part "R-EU_R0603E"))
    )
    (comp (ref "R46")
      (value "1200971020**RES 0603 10K %1 1/10W")
      (footprint "eagle-import:R0603_ENKO")
      (libsource (lib "eagle-import") (part "R-EU_R0603E"))
    )
    (comp (ref "R47")
      (value "1200971020**RES 0603 10K %1 1/10W")
      (footprint "eagle-import:R0603_ENKO")
      (libsource (lib "eagle-import") (part "R-EU_R0603E"))
    )
    (comp (ref "R48")
      (value "1200970516**RES 0603 22K %5 1/10W")
      (footprint "eagle-import:R0603_ENKO")
      (libsource (lib "eagle-import") (part "R-EU_R0603E"))
    )
    (comp (ref "R49")
      (value "1029-2005**RES 0603 220R %1")
      (footprint "eagle-import:R0603_ENKO")
      (libsource (lib "eagle-import") (part "R-EU_R0603E"))
    )
    (comp (ref "R50")
      (value "1200970803**RES 0603 100K %1 1/10W")
      (footprint "eagle-import:R0603_ENKO")
      (libsource (lib "eagle-import") (part "R-EU_R0603E"))
    )
    (comp (ref "R51")
      (value "1200971020**RES 0603 10K %1 1/10W")
      (footprint "eagle-import:R0603_ENKO")
      (libsource (lib "eagle-import") (part "R-EU_R0603E"))
    )
    (comp (ref "R52")
      (value "1029-2005**RES 0603 220R %1")
      (footprint "eagle-import:R0603_ENKO")
      (libsource (lib "eagle-import") (part "R-EU_R0603E"))
    )
    (comp (ref "R53")
      (value "1029-2005**RES 0603 220R %1")
      (footprint "eagle-import:R0603_ENKO")
      (libsource (lib "eagle-import") (part "R-EU_R0603E"))
    )
    (comp (ref "R54")
      (value "1200971020**RES 0603 10K %1 1/10W")
      (footprint "eagle-import:R0603_ENKO")
      (libsource (lib "eagle-import") (part "R-EU_R0603E"))
    )
    (comp (ref "R55")
      (value "1029-2233**RES 0603 2K2 %1")
      (footprint "eagle-import:R0603_ENKO")
      (libsource (lib "eagle-import") (part "R-EU_R0603E"))
    )
    (comp (ref "R56")
      (value "1200970522**RES 0603 1K %5 1/10W")
      (footprint "eagle-import:R0603_ENKO")
      (libsource (lib "eagle-import") (part "R-EU_R0603E"))
    )
    (comp (ref "R57")
      (value "1200970803**RES 0603 100K %1 1/10W")
      (footprint "eagle-import:R0603_ENKO")
      (libsource (lib "eagle-import") (part "R-EU_R0603E"))
    )
    (comp (ref "R58")
      (value "1200970770**RES 0603 4K3 %1 1/10W")
      (footprint "eagle-import:R0603_ENKO")
      (libsource (lib "eagle-import") (part "R-EU_R0603E"))
    )
    (comp (ref "R59")
      (value "1200970803**RES 0603 100K %1 1/10W")
      (footprint "eagle-import:R0603_ENKO")
      (libsource (lib "eagle-import") (part "R-EU_R0603E"))
    )
    (comp (ref "R60")
      (value "1029-2234**RES 0603 4K7 %1")
      (footprint "eagle-import:R0603_ENKO")
      (libsource (lib "eagle-import") (part "R-EU_R0603E"))
    )
    (comp (ref "R61")
      (value "1200970583**RES 0603 1K %1 1/10W")
      (footprint "eagle-import:R0603_ENKO")
      (libsource (lib "eagle-import") (part "R-EU_R0603E"))
    )
    (comp (ref "R62")
      (value "1200970706**RES 0603 1K8 %5 1/10W")
      (footprint "eagle-import:R0603_ENKO")
      (libsource (lib "eagle-import") (part "R-EU_R0603E"))
    )
    (comp (ref "R63")
      (value "1029-2003**RES 0603 10R %1")
      (footprint "eagle-import:R0603_ENKO")
      (libsource (lib "eagle-import") (part "R-EU_R0603E"))
    )
    (comp (ref "R64")
      (value "1029-2006**RES 0603 47R %1")
      (footprint "eagle-import:R0603_ENKO")
      (libsource (lib "eagle-import") (part "R-EU_R0603E"))
    )
    (comp (ref "R65")
      (value "1029-6021**RES 2512 0R003 %1 2W")
      (footprint "eagle-import:R2512")
      (libsource (lib "eagle-import") (part "R-EU_R2512"))
    )
    (comp (ref "R66")
      (value "1200970927**RES 0603 100R %1 1/10W")
      (footprint "eagle-import:R0603_ENKO")
      (libsource (lib "eagle-import") (part "R-EU_R0603E"))
    )
    (comp (ref "R67")
      (value "1200970522**RES 0603 1K %5 1/10W")
      (footprint "eagle-import:R0603_ENKO")
      (libsource (lib "eagle-import") (part "R-EU_R0603E"))
    )
    (comp (ref "R68")
      (value "1200970522**RES 0603 1K %5 1/10W")
      (footprint "eagle-import:R0603_ENKO")
      (libsource (lib "eagle-import") (part "R-EU_R0603E"))
    )
    (comp (ref "R69")
      (value "1029-3008**RES 0805 22R %5")
      (footprint "eagle-import:R0805_ENKO")
      (libsource (lib "eagle-import") (part "R-EU_R0805E"))
    )
    (comp (ref "R70")
      (value "1200970843**RES 0603 15K %1 1/10W")
      (footprint "eagle-import:R0603_ENKO")
      (libsource (lib "eagle-import") (part "R-EU_R0603E"))
    )
    (comp (ref "R71")
      (value "1029-2234**RES 0603 4K7 %1")
      (footprint "eagle-import:R0603_ENKO")
      (libsource (lib "eagle-import") (part "R-EU_R0603E"))
    )
    (comp (ref "R72")
      (value "1200970583**RES 0603 1K %1 1/10W")
      (footprint "eagle-import:R0603_ENKO")
      (libsource (lib "eagle-import") (part "R-EU_R0603E"))
    )
    (comp (ref "R74")
      (value "1200970194**RES 1206 4K7 %5 1/4W")
      (footprint "eagle-import:R1206_ENKO")
      (libsource (lib "eagle-import") (part "R-EU_R1206E"))
    )
    (comp (ref "R75")
      (value "1200970583**RES 0603 1K %1 1/10W")
      (footprint "eagle-import:R0603_ENKO")
      (libsource (lib "eagle-import") (part "R-EU_R0603E"))
    )
    (comp (ref "R76")
      (value "1200970684**RES 0603 47K %1 1/10W")
      (footprint "eagle-import:R0603_ENKO")
      (libsource (lib "eagle-import") (part "R-EU_R0603E"))
    )
    (comp (ref "R77")
      (value "1029-6089**RES 0603 6K8 %5")
      (footprint "eagle-import:R0603_ENKO")
      (libsource (lib "eagle-import") (part "R-EU_R0603E"))
    )
    (comp (ref "R78")
      (value "1029-2203**RES 0603 12K %1")
      (footprint "eagle-import:R0603_ENKO")
      (libsource (lib "eagle-import") (part "R-EU_R0603E"))
    )
    (comp (ref "R79")
      (value "1029-2341**RES 0603 5K6 %1")
      (footprint "eagle-import:R0603_ENKO")
      (libsource (lib "eagle-import") (part "R-EU_R0603E"))
    )
    (comp (ref "R80")
      (value "1029-2234**RES 0603 4K7 %1")
      (footprint "eagle-import:R0603_ENKO")
      (libsource (lib "eagle-import") (part "R-EU_R0603E"))
    )
    (comp (ref "R81")
      (value "1200970583**RES 0603 1K %1 1/10W")
      (footprint "eagle-import:R0603_ENKO")
      (libsource (lib "eagle-import") (part "R-EU_R0603E"))
    )
    (comp (ref "R82")
      (value "1200971020**RES 0603 10K %1 1/10W")
      (footprint "eagle-import:R0603_ENKO")
      (libsource (lib "eagle-import") (part "R-EU_R0603E"))
    )
    (comp (ref "R83")
      (value "1200970522**RES 0603 1K %5 1/10W")
      (footprint "eagle-import:R0603_ENKO")
      (libsource (lib "eagle-import") (part "R-EU_R0603E"))
    )
    (comp (ref "R84")
      (value "1200970522**RES 0603 1K %5 1/10W")
      (footprint "eagle-import:R0603_ENKO")
      (libsource (lib "eagle-import") (part "R-EU_R0603E"))
    )
    (comp (ref "R86")
      (value "1200970522**RES 0603 1K %5 1/10W")
      (footprint "eagle-import:R0603_ENKO")
      (libsource (lib "eagle-import") (part "R-EU_R0603E"))
    )
    (comp (ref "R87")
      (value "1200971020**RES 0603 10K %1 1/10W")
      (footprint "eagle-import:R0603_ENKO")
      (libsource (lib "eagle-import") (part "R-EU_R0603E"))
    )
    (comp (ref "R88")
      (value "1029-2234**RES 0603 4K7 %1")
      (footprint "eagle-import:R0603_ENKO")
      (libsource (lib "eagle-import") (part "R-EU_R0603E"))
    )
    (comp (ref "R89")
      (value "1200970583**RES 0603 1K %1 1/10W")
      (footprint "eagle-import:R0603_ENKO")
      (libsource (lib "eagle-import") (part "R-EU_R0603E"))
    )
    (comp (ref "R90")
      (value "1029-2231**RES 0603 1K8 %1")
      (footprint "eagle-import:R0603_ENKO")
      (libsource (lib "eagle-import") (part "R-EU_R0603E"))
    )
    (comp (ref "R91")
      (value "1200971020**RES 0603 10K %1 1/10W")
      (footprint "eagle-import:R0603_ENKO")
      (libsource (lib "eagle-import") (part "R-EU_R0603E"))
    )
    (comp (ref "R92")
      (value "1200970568**RES 0603 47K %5 1/10W")
      (footprint "eagle-import:R0603_ENKO")
      (libsource (lib "eagle-import") (part "R-EU_R0603E"))
    )
    (comp (ref "R93")
      (value "1409-0025**RES 0603 470R %5 1/16W")
      (footprint "eagle-import:R0603_ENKO")
      (libsource (lib "eagle-import") (part "R-EU_R0603E"))
    )
    (comp (ref "R94")
      (value "1029-6086**RES 0603 22R %1")
      (footprint "eagle-import:R0603_ENKO")
      (libsource (lib "eagle-import") (part "R-EU_R0603E"))
    )
    (comp (ref "R95")
      (value "1200970583**RES 0603 1K %1 1/10W")
      (footprint "eagle-import:R0603_ENKO")
      (libsource (lib "eagle-import") (part "R-EU_R0603E"))
    )
    (comp (ref "R96")
      (value "1029-6086**RES 0603 22R %1")
      (footprint "eagle-import:R0603_ENKO")
      (libsource (lib "eagle-import") (part "R-EU_R0603E"))
    )
    (comp (ref "R97")
      (value "1029-6086**RES 0603 22R %1")
      (footprint "eagle-import:R0603_ENKO")
      (libsource (lib "eagle-import") (part "R-EU_R0603E"))
    )
    (comp (ref "R98")
      (value "1029-2234**RES 0603 4K7 %1")
      (footprint "eagle-import:R0603_ENKO")
      (libsource (lib "eagle-import") (part "R-EU_R0603E"))
    )
    (comp (ref "R99")
      (value "1200970516**RES 0603 22K %5 1/10W")
      (footprint "eagle-import:R0603_ENKO")
      (libsource (lib "eagle-import") (part "R-EU_R0603E"))
    )
    (comp (ref "R100")
      (value "1200970852**RES 0603 1K5 %5 1/10W ( <-1029-3501 )")
      (footprint "eagle-import:R0603_ENKO")
      (libsource (lib "eagle-import") (part "R-EU_R0603E"))
    )
    (comp (ref "R101")
      (value "1200970684**RES 0603 47K %1 1/10W")
      (footprint "eagle-import:R0603_ENKO")
      (libsource (lib "eagle-import") (part "R-EU_R0603E"))
    )
    (comp (ref "R102")
      (value "1200970583**RES 0603 1K %1 1/10W")
      (footprint "eagle-import:R0603_ENKO")
      (libsource (lib "eagle-import") (part "R-EU_R0603E"))
    )
    (comp (ref "R103")
      (value "1200970522**RES 0603 1K %5 1/10W")
      (footprint "eagle-import:R0603_ENKO")
      (libsource (lib "eagle-import") (part "R-EU_R0603E"))
    )
    (comp (ref "R104")
      (value "1200970522**RES 0603 1K %5 1/10W")
      (footprint "eagle-import:R0603_ENKO")
      (libsource (lib "eagle-import") (part "R-EU_R0603E"))
    )
    (comp (ref "R105")
      (value "1029-2229**RES 0603 120K %1")
      (footprint "eagle-import:R0603_ENKO")
      (libsource (lib "eagle-import") (part "R-EU_R0603E"))
    )
    (comp (ref "R106")
      (value "1029-2219**RES 0603 30K %1")
      (footprint "eagle-import:R0603_ENKO")
      (libsource (lib "eagle-import") (part "R-EU_R0603E"))
    )
    (comp (ref "R107")
      (value "1200970515**RES 0603 100K %5 1/10W")
      (footprint "eagle-import:R0603_ENKO")
      (libsource (lib "eagle-import") (part "R-EU_R0603E"))
    )
    (comp (ref "R108")
      (value "1200970730**RES 0603 560R %1 1/10W")
      (footprint "eagle-import:R0603_ENKO")
      (libsource (lib "eagle-import") (part "R-EU_R0603E"))
    )
    (comp (ref "R109")
      (value "1200971020**RES 0603 10K %1 1/10W")
      (footprint "eagle-import:R0603_ENKO")
      (libsource (lib "eagle-import") (part "R-EU_R0603E"))
    )
    (comp (ref "R110")
      (value "1200970516**RES 0603 22K %5 1/10W")
      (footprint "eagle-import:R0603_ENKO")
      (libsource (lib "eagle-import") (part "R-EU_R0603E"))
    )
    (comp (ref "R111")
      (value "NC**TAKILMAYACAK")
      (footprint "eagle-import:R0603_ENKO")
      (libsource (lib "eagle-import") (part "R-EU_R0603E"))
    )
    (comp (ref "R112")
      (value "1200970156**RES 1206 22K %5 1/4W")
      (footprint "eagle-import:R1206_ENKO")
      (libsource (lib "eagle-import") (part "R-EU_R1206E"))
    )
    (comp (ref "R113")
      (value "1200970121**RES 0805 1K %5 1/8W")
      (footprint "eagle-import:R0805_ENKO")
      (libsource (lib "eagle-import") (part "R-EU_R0805E"))
    )
    (comp (ref "R114")
      (value "1200971020**RES 0603 10K %1 1/10W")
      (footprint "eagle-import:R0603_ENKO")
      (libsource (lib "eagle-import") (part "R-EU_R0603E"))
    )
    (comp (ref "R115")
      (value "1200970156**RES 1206 22K %5 1/4W")
      (footprint "eagle-import:R1206_ENKO")
      (libsource (lib "eagle-import") (part "R-EU_R1206E"))
    )
    (comp (ref "R116")
      (value "1200970585**RES 0603 1M %5 1/10W")
      (footprint "eagle-import:R0603_ENKO")
      (libsource (lib "eagle-import") (part "R-EU_R0603E"))
    )
    (comp (ref "R117")
      (value "1029-6015**RES 1206 56K %5")
      (footprint "eagle-import:R1206_ENKO")
      (libsource (lib "eagle-import") (part "R-EU_R1206E"))
    )
    (comp (ref "R118")
      (value "1029-6105**RES 2512 330mR %1 2W")
      (footprint "eagle-import:R2512")
      (libsource (lib "eagle-import") (part "R-EU_R2512"))
    )
    (comp (ref "R119")
      (value "1029-6105**RES 2512 330mR %1 2W")
      (footprint "eagle-import:R2512")
      (libsource (lib "eagle-import") (part "R-EU_R2512"))
    )
    (comp (ref "R122")
      (value "1200970516**RES 0603 22K %5 1/10W")
      (footprint "eagle-import:R0603_ENKO")
      (libsource (lib "eagle-import") (part "R-EU_R0603E"))
    )
    (comp (ref "R123")
      (value "1200970522**RES 0603 1K %5 1/10W")
      (footprint "eagle-import:R0603_ENKO")
      (libsource (lib "eagle-import") (part "R-EU_R0603E"))
    )
    (comp (ref "R124")
      (value "1200970522**RES 0603 1K %5 1/10W")
      (footprint "eagle-import:R0603_ENKO")
      (libsource (lib "eagle-import") (part "R-EU_R0603E"))
    )
    (comp (ref "R125")
      (value "1200970516**RES 0603 22K %5 1/10W")
      (footprint "eagle-import:R0603_ENKO")
      (libsource (lib "eagle-import") (part "R-EU_R0603E"))
    )
    (comp (ref "R127")
      (value "1200971020**RES 0603 10K %1 1/10W")
      (footprint "eagle-import:R0603_ENKO")
      (libsource (lib "eagle-import") (part "R-EU_R0603E"))
    )
    (comp (ref "R133")
      (value "1200970626**RES 0603 82K %1 1/10W")
      (footprint "eagle-import:R0603_ENKO")
      (libsource (lib "eagle-import") (part "R-EU_R0603E"))
    )
    (comp (ref "R134")
      (value "1029-2234**RES 0603 4K7 %1")
      (footprint "eagle-import:R0603_ENKO")
      (libsource (lib "eagle-import") (part "R-EU_R0603E"))
    )
    (comp (ref "R135")
      (value "1200970940**RES 0603 6K8 %1 1/10W")
      (footprint "eagle-import:R0603_ENKO")
      (libsource (lib "eagle-import") (part "R-EU_R0603E"))
    )
    (comp (ref "R193")
      (value "1200970934**RES 0603 470K %1 1/10W")
      (footprint "eagle-import:R0603_ENKO")
      (libsource (lib "eagle-import") (part "R-EU_R0603E"))
    )
    (comp (ref "R194")
      (value "1200970528**RES 0603 0R %5 1/10W")
      (footprint "eagle-import:R0603_ENKO")
      (libsource (lib "eagle-import") (part "R-EU_R0603E"))
    )
    (comp (ref "RF1")
      (value "1169-1006**FUSE SMD 1206 PTC RESETTABLE 16V IHOLD=0.75A IMAX=100A")
      (footprint "eagle-import:R1206_ENKO")
      (libsource (lib "eagle-import") (part "R-EU_R1206E"))
    )
    (comp (ref "RL1")
      (value "1200930051**RELAY SPST 12V 5A 7x15x20.3mm")
      (footprint "eagle-import:ALD1_AND_ALJ_RELAY")
      (libsource (lib "eagle-import") (part "ALD1_AND_ALJ_RELAY"))
    )
    (comp (ref "STENCIL")
      (value "041-7604**SDA381V8 için Çerçeveli Elek (Stencil) (600x600)")
      (footprint "eagle-import:PCB")
      (libsource (lib "eagle-import") (part "PCB"))
    )
    (comp (ref "T1")
      (value "1109-1016**Transistor NPN 3A 100V 15W Hfemin:10 DPAK Diodes MJD31C-13")
      (footprint "eagle-import:DPAK")
      (libsource (lib "eagle-import") (part "MJD31C"))
    )
    (comp (ref "T1_X")
      (value "NC**TAKILMAYACAK (Not Fitted)")
      (footprint "eagle-import:SOT23-BEC")
      (libsource (lib "eagle-import") (part "-NPN-SOT23-BECBC846"))
    )
    (comp (ref "T2")
      (value "1200980090**TRANS SMD NPN BC847B SOT-23")
      (footprint "eagle-import:SOT23-BEC")
      (libsource (lib "eagle-import") (part "-NPN-SOT23-BECBC846"))
    )
    (comp (ref "T3")
      (value "1200980091**TRANS SMD PNP BC857B SOT-23")
      (footprint "eagle-import:SOT23-BEC")
      (libsource (lib "eagle-import") (part "-PNP-SOT23-BECBC856B"))
    )
    (comp (ref "T4")
      (value "1200980090**TRANS SMD NPN BC847B SOT-23")
      (footprint "eagle-import:SOT23-BEC")
      (libsource (lib "eagle-import") (part "-NPN-SOT23-BECBC846"))
    )
    (comp (ref "T5")
      (value "1200980090**TRANS SMD NPN BC847B SOT-23")
      (footprint "eagle-import:SOT23-BEC")
      (libsource (lib "eagle-import") (part "-NPN-SOT23-BECBC846"))
    )
    (comp (ref "T6")
      (value "1200980090**TRANS SMD NPN BC847B SOT-23")
      (footprint "eagle-import:SOT23-BEC")
      (libsource (lib "eagle-import") (part "-NPN-SOT23-BECBC846"))
    )
    (comp (ref "T7")
      (value "1200980090**TRANS SMD NPN BC847B SOT-23")
      (footprint "eagle-import:SOT23-BEC")
      (libsource (lib "eagle-import") (part "-NPN-SOT23-BECBC846"))
    )
    (comp (ref "T9")
      (value "1200980090**TRANS SMD NPN BC847B SOT-23")
      (footprint "eagle-import:SOT23-BEC")
      (libsource (lib "eagle-import") (part "-NPN-SOT23-BECBC846"))
    )
    (comp (ref "T10")
      (value "1049-1012**MMBTA56 PNP 80V 500mA 330mW hfe(min):100 SOT23")
      (footprint "eagle-import:SOT23-BEC")
      (libsource (lib "eagle-import") (part "-PNP-SOT23-BECBC856B"))
    )
    (comp (ref "TRF1")
      (value "0319-7458**SMPS TRAFO 90W E36/18/11 2*60uH (Insulation Improved 0319-7451) DBC2")
      (footprint "eagle-import:DEIF_TRF")
      (libsource (lib "eagle-import") (part "DEIF_TRF"))
    )
    (comp (ref "TVS1")
      (value "1119-3061**5V 130W TVS Diode SOD-323")
      (footprint "eagle-import:SOD323")
      (libsource (lib "eagle-import") (part "TVS-BD-SOD323"))
    )
    (comp (ref "U1")
      (value "1039-2220**STM32F072C8T6 64K Flash USB, CAN")
      (footprint "eagle-import:STM32F072CXXX_LQFP48")
      (libsource (lib "eagle-import") (part "STM32F072CXXX_LQFP48"))
    )
    (comp (ref "U2")
      (value "1039-2392**LMR16006XDDCR 0.6A, 0.7MHz Step-Down Converter in a TSOT-6L, Input 4V to 60V")
      (footprint "eagle-import:AOZ1282CI-1")
      (libsource (lib "eagle-import") (part "AOZ1282CI-1"))
    )
    (comp (ref "VR1")
      (value "0169-2013**Varistor 20mm 300V")
      (footprint "eagle-import:S20K40")
      (libsource (lib "eagle-import") (part "S20K40"))
    )
    (comp (ref "X1")
      (value "0289-1472**WR-TBL Series 3134 - 3 kutup 7.62 mm Close Hor. PCB Header (Wurth 691 313 410 003)")
      (footprint "eagle-import:GMSTBA3")
      (fields (field (name "MF") "FARNELL") (field (name "MPN") "1757255"))
      (libsource (lib "eagle-import") (part "GMSTBA3"))
    )
    (comp (ref "X1-K")
      (value "0289-1473**WR-TBL Series 3524 - 3 kutup 7.62 mm Hor. w. Hook on Wire Side (Wurth 691 352 410 003)")
      (footprint "eagle-import:SOKET")
      (libsource (lib "eagle-import") (part "SOKET"))
    )
    (comp (ref "X2")
      (value "0309-1064**USB Type-B Mini Connector Horizantal")
      (footprint "eagle-import:USB_B(YATIK)")
      (libsource (lib "eagle-import") (part "USB_B(YATIK)"))
    )
    (comp (ref "X3")
      (value "0289-1470**WR-TBL Series 313 - 4 kutup 5.08 mm Close Hor. PCB Header (Wurth 691 313 510 004)")
      (footprint "eagle-import:MSTBA4")
      (fields (field (name "MF") "FARNELL") (field (name "MPN") "1757268"))
      (libsource (lib "eagle-import") (part "MSTBA4"))
    )
    (comp (ref "X3-K")
      (value "0289-1471**WR-TBL Series 352 - 4 kutup 5.08 mm Hor. with Hook on Wire Side (wurth 691 352 510 004)")
      (footprint "eagle-import:SOKET")
      (libsource (lib "eagle-import") (part "SOKET"))
    )
    (comp (ref "X4")
      (value "0289-1474**WR-TBL Series 313 - 3 kutup 5.08 mm Close Hor. PCB Header (Wurth 691 313 510 003)")
      (footprint "eagle-import:MSTBA3")
      (fields (field (name "MF") "FARNELL") (field (name "MPN") "1757255"))
      (libsource (lib "eagle-import") (part "MSTBA3"))
    )
    (comp (ref "X4-K")
      (value "0289-1475**WR-TBL Series 352 - 3 kutup 5.08 mm Hor. with Hook on Wire Side (wurth 691 352 510 003)")
      (footprint "eagle-import:SOKET")
      (libsource (lib "eagle-import") (part "SOKET"))
    )
    (comp (ref "Y1")
      (value "1149-0013**Crystal 16MHz ±10ppm 10pF 120 Ohms 4-SMD, No Lead 2.00mm x 1.60mm")
      (footprint "eagle-import:NX2016SA-32M")
      (libsource (lib "eagle-import") (part "NX2016SA-32M"))
    )
    (comp (ref "Z1")
      (value "1129-1195**ZENER SOT23 18V 400mW %5 BZX84C18V")
      (footprint "eagle-import:SOT23")
      (libsource (lib "eagle-import") (part "ZENER-DIODESOT23"))
    )
    (comp (ref "Z3")
      (value "1129-1146**ZENER SOT23 2V7 300mW BZX84C2V7")
      (footprint "eagle-import:SOT23")
      (libsource (lib "eagle-import") (part "ZENER-DIODESOT23"))
    )
    (comp (ref "Z4")
      (value "1129-1162**ZENER SOT23 3V9 300mW BZX84C3V9")
      (footprint "eagle-import:SOT23")
      (libsource (lib "eagle-import") (part "ZENER-DIODESOT23"))
    )
    (comp (ref "Z5")
      (value "1129-1151**ZENER SOT23 12V 225mW BZX84C12")
      (footprint "eagle-import:SOT23")
      (libsource (lib "eagle-import") (part "ZENER-DIODESOT23"))
    )
    (comp (ref "Z6")
      (value "1129-1146**ZENER SOT23 2V7 300mW BZX84C2V7")
      (footprint "eagle-import:SOT23")
      (libsource (lib "eagle-import") (part "ZENER-DIODESOT23"))
    )
    (comp (ref "Z7")
      (value "1129-1151**ZENER SOT23 12V 225mW BZX84C12")
      (footprint "eagle-import:SOT23")
      (libsource (lib "eagle-import") (part "ZENER-DIODESOT23"))
    )
    (comp (ref "Z8")
      (value "1129-1140**ZENER SOT23 5V1 0.4W BZX84C5V1")
      (footprint "eagle-import:SOT23")
      (libsource (lib "eagle-import") (part "ZENER-DIODESOT23"))
    )
  )
  (nets
    (net (code "1") (name "+3V3") (class "Default")
      (node (ref "C38") (pin "1") (pinfunction "1_1") (pintype "passive"))
      (node (ref "C39") (pin "1") (pinfunction "1_1") (pintype "passive"))
      (node (ref "C45") (pin "1") (pinfunction "1_1") (pintype "passive"))
      (node (ref "C48") (pin "1") (pinfunction "1_1") (pintype "passive"))
      (node (ref "C49") (pin "1") (pinfunction "1_1") (pintype "passive"))
      (node (ref "C51") (pin "1") (pinfunction "1_1") (pintype "passive"))
      (node (ref "C54") (pin "1") (pinfunction "1_1") (pintype "passive"))
      (node (ref "C55") (pin "1") (pinfunction "1_1") (pintype "passive"))
      (node (ref "C57") (pin "1") (pinfunction "1_1") (pintype "passive"))
      (node (ref "D13") (pin "2") (pinfunction "C_2") (pintype "passive"))
      (node (ref "FB4") (pin "2") (pinfunction "2_2") (pintype "passive"))
      (node (ref "IC4") (pin "3") (pinfunction "OUT_3") (pintype "passive"))
      (node (ref "IC5") (pin "8") (pinfunction "V+_8") (pintype "power_in"))
      (node (ref "LED1") (pin "2") (pinfunction "2_2") (pintype "passive"))
      (node (ref "PROG1") (pin "1") (pinfunction "+3V3_1") (pintype "passive"))
      (node (ref "R100") (pin "2") (pinfunction "2_2") (pintype "passive"))
      (node (ref "R46") (pin "1") (pinfunction "1_1") (pintype "passive"))
      (node (ref "R72") (pin "2") (pinfunction "2_2") (pintype "passive"))
      (node (ref "U1") (pin "24") (pinfunction "VDD._24") (pintype "bidirectional"))
      (node (ref "U1") (pin "36") (pinfunction "VDDIO2_36") (pintype "bidirectional"))
      (node (ref "U1") (pin "48") (pinfunction "VDD_48") (pintype "bidirectional"))
    )
    (net (code "2") (name "/13.8V+") (class "Default")
      (node (ref "C18") (pin "P$1") (pinfunction "1_P$1") (pintype "passive"))
      (node (ref "C24") (pin "P$1") (pinfunction "1_P$1") (pintype "passive"))
      (node (ref "C36") (pin "1") (pinfunction "1_1") (pintype "passive"))
      (node (ref "C37") (pin "1") (pinfunction "1_1") (pintype "passive"))
      (node (ref "C40") (pin "+") (pinfunction "+_+") (pintype "passive"))
      (node (ref "C40") (pin "+1") (pinfunction "+_+1") (pintype "passive"))
      (node (ref "C42") (pin "+") (pinfunction "+_+") (pintype "passive"))
      (node (ref "C72") (pin "2") (pinfunction "2_2") (pintype "passive"))
      (node (ref "C73") (pin "1") (pinfunction "1_1") (pintype "passive"))
      (node (ref "C74") (pin "P$1") (pinfunction "1_P$1") (pintype "passive"))
      (node (ref "C84") (pin "+") (pinfunction "+_+") (pintype "passive"))
      (node (ref "C84_X") (pin "+") (pinfunction "+_+") (pintype "passive"))
      (node (ref "C85") (pin "1") (pinfunction "1_1") (pintype "passive"))
      (node (ref "C86") (pin "1") (pinfunction "1_1") (pintype "passive"))
      (node (ref "C88") (pin "P$1") (pinfunction "1_P$1") (pintype "passive"))
      (node (ref "D7") (pin "A") (pinfunction "A_A") (pintype "passive"))
      (node (ref "OC2") (pin "1") (pinfunction "1_1") (pintype "passive"))
      (node (ref "R110") (pin "2") (pinfunction "2_2") (pintype "passive"))
      (node (ref "R117") (pin "1") (pinfunction "1_1") (pintype "passive"))
      (node (ref "R127") (pin "2") (pinfunction "2_2") (pintype "passive"))
      (node (ref "R50") (pin "1") (pinfunction "1_1") (pintype "passive"))
      (node (ref "R78") (pin "2") (pinfunction "2_2") (pintype "passive"))
      (node (ref "TRF1") (pin "10") (pinfunction "13_10") (pintype "passive"))
      (node (ref "TRF1") (pin "21") (pinfunction "13_21") (pintype "passive"))
      (node (ref "TRF1") (pin "22") (pinfunction "12_22") (pintype "passive"))
      (node (ref "TRF1") (pin "29") (pinfunction "12_29") (pintype "passive"))
      (node (ref "TRF1") (pin "30") (pinfunction "13_30") (pintype "passive"))
      (node (ref "TRF1") (pin "43") (pinfunction "12_43") (pintype "passive"))
      (node (ref "TRF1") (pin "44") (pinfunction "13_44") (pintype "passive"))
      (node (ref "TRF1") (pin "9") (pinfunction "12_9") (pintype "passive"))
      (node (ref "X3") (pin "1") (pinfunction "1_1") (pintype "passive"))
    )
    (net (code "3") (name "/I_FOR_REV_BAT_PROTEC") (class "Default")
      (node (ref "C50") (pin "2") (pinfunction "2_2") (pintype "passive"))
      (node (ref "IC5") (pin "3") (pinfunction "+IN_3") (pintype "input"))
      (node (ref "IC5") (pin "7") (pinfunction "OUT_7") (pintype "output"))
      (node (ref "R109") (pin "2") (pinfunction "2_2") (pintype "passive"))
      (node (ref "R5") (pin "2") (pinfunction "2_2") (pintype "passive"))
      (node (ref "R71") (pin "2") (pinfunction "2_2") (pintype "passive"))
    )
    (net (code "4") (name "/N$84") (class "Default")
      (node (ref "C21") (pin "2") (pinfunction "2_2") (pintype "passive"))
      (node (ref "C21") (pin "4") (pinfunction "2_4") (pintype "passive"))
      (node (ref "IC2") (pin "6") (pinfunction "6.CS_6") (pintype "input"))
      (node (ref "Q2") (pin "D") (pinfunction "D_D") (pintype "passive"))
      (node (ref "TRF1") (pin "11") (pinfunction "14_11") (pintype "passive"))
      (node (ref "TRF1") (pin "12") (pinfunction "15_12") (pintype "passive"))
      (node (ref "TRF1") (pin "13") (pinfunction "16_13") (pintype "passive"))
      (node (ref "TRF1") (pin "19") (pinfunction "15_19") (pintype "passive"))
      (node (ref "TRF1") (pin "20") (pinfunction "14_20") (pintype "passive"))
      (node (ref "TRF1") (pin "25") (pinfunction "16_25") (pintype "passive"))
      (node (ref "TRF1") (pin "31") (pinfunction "14_31") (pintype "passive"))
      (node (ref "TRF1") (pin "32") (pinfunction "15_32") (pintype "passive"))
      (node (ref "TRF1") (pin "38") (pinfunction "16_38") (pintype "passive"))
      (node (ref "TRF1") (pin "45") (pinfunction "14_45") (pintype "passive"))
      (node (ref "TRF1") (pin "46") (pinfunction "15_46") (pintype "passive"))
      (node (ref "TRF1") (pin "47") (pinfunction "16_47") (pintype "passive"))
    )
    (net (code "5") (name "/OUT_EN") (class "Default")
      (node (ref "C71") (pin "1") (pinfunction "1_1") (pintype "passive"))
      (node (ref "D14") (pin "A") (pinfunction "A_A") (pintype "passive"))
      (node (ref "R110") (pin "1") (pinfunction "1_1") (pintype "passive"))
      (node (ref "T2") (pin "C") (pinfunction "C_C") (pintype "passive"))
    )
    (net (code "6") (name "/PRI_SOURCE") (class "Default")
      (node (ref "C22") (pin "P$2") (pinfunction "2_P$2") (pintype "passive"))
      (node (ref "C25") (pin "2") (pinfunction "2_2") (pintype "passive"))
      (node (ref "HS1") (pin "1") (pinfunction "P$1_1") (pintype "power_in"))
      (node (ref "HS1") (pin "2") (pinfunction "P$1_2") (pintype "power_in"))
      (node (ref "Q1") (pin "S") (pinfunction "S_S") (pintype "passive"))
      (node (ref "R118") (pin "2") (pinfunction "2_2") (pintype "passive"))
      (node (ref "R119") (pin "2") (pinfunction "2_2") (pintype "passive"))
      (node (ref "R21") (pin "1") (pinfunction "1_1") (pintype "passive"))
      (node (ref "R27") (pin "1") (pinfunction "1_1") (pintype "passive"))
      (node (ref "R6") (pin "2") (pinfunction "2_2") (pintype "passive"))
    )
    (net (code "7") (name "/REG_INP") (class "Default")
      (node (ref "C47") (pin "1") (pinfunction "1_1") (pintype "passive"))
      (node (ref "D8") (pin "C") (pinfunction "C_C") (pintype "passive"))
      (node (ref "D9") (pin "3") (pinfunction "C_3") (pintype "passive"))
      (node (ref "IC4") (pin "2") (pinfunction "IN_2") (pintype "input"))
      (node (ref "IC4") (pin "4") (pinfunction "IN_4") (pintype "input"))
    )
    (net (code "8") (name "/RES") (class "Default")
      (node (ref "C28") (pin "2") (pinfunction "2_2") (pintype "passive"))
      (node (ref "IC2") (pin "4") (pinfunction "4.LLD_4") (pintype "input"))
      (node (ref "R44") (pin "1") (pinfunction "1_1") (pintype "passive"))
    )
    (net (code "9") (name "/VDC_BUS") (class "Default")
      (node (ref "B1") (pin "+") (pinfunction "+_+") (pintype "passive"))
      (node (ref "C11") (pin "1") (pinfunction "1_1") (pintype "passive"))
      (node (ref "C12") (pin "+") (pinfunction "+_+") (pintype "passive"))
      (node (ref "C24") (pin "P$2") (pinfunction "2_P$2") (pintype "passive"))
      (node (ref "C27") (pin "2") (pinfunction "2_2") (pintype "passive"))
      (node (ref "C76") (pin "1") (pinfunction "1_1") (pintype "passive"))
      (node (ref "C82") (pin "1") (pinfunction "1_1") (pintype "passive"))
      (node (ref "D2") (pin "A") (pinfunction "A_A") (pintype "passive"))
      (node (ref "D3") (pin "A") (pinfunction "A_A") (pintype "passive"))
      (node (ref "R11") (pin "2") (pinfunction "2_2") (pintype "passive"))
      (node (ref "R9") (pin "2") (pinfunction "2_2") (pintype "passive"))
      (node (ref "TRF1") (pin "16") (pinfunction "4_16") (pintype "passive"))
      (node (ref "TRF1") (pin "3") (pinfunction "4_3") (pintype "passive"))
      (node (ref "TRF1") (pin "35") (pinfunction "4_35") (pintype "passive"))
      (node (ref "TRF1") (pin "52") (pinfunction "4_52") (pintype "passive"))
    )
    (net (code "10") (name "/VREF2.1") (class "Default")
      (node (ref "IC3") (pin "1") (pinfunction "VREF_1") (pintype "bidirectional"))
      (node (ref "IC3") (pin "5") (pinfunction "CV+_5") (pintype "input"))
      (node (ref "R61") (pin "2") (pinfunction "2_2") (pintype "passive"))
    )
    (net (code "11") (name "/V_FB2") (class "Default")
      (node (ref "C78") (pin "1") (pinfunction "1_1") (pintype "passive"))
      (node (ref "R134") (pin "1") (pinfunction "1_1") (pintype "passive"))
      (node (ref "R135") (pin "2") (pinfunction "2_2") (pintype "passive"))
      (node (ref "U2") (pin "3") (pinfunction "FB_3") (pintype "bidirectional"))
    )
    (net (code "12") (name "/V_SUPPLY") (class "Default")
      (node (ref "C33") (pin "2") (pinfunction "2_2") (pintype "passive"))
      (node (ref "C34") (pin "2") (pinfunction "2_2") (pintype "passive"))
      (node (ref "C61") (pin "1") (pinfunction "1_1") (pintype "passive"))
      (node (ref "C69") (pin "2") (pinfunction "2_2") (pintype "passive"))
      (node (ref "C79") (pin "2") (pinfunction "2_2") (pintype "passive"))
      (node (ref "C98") (pin "2") (pinfunction "2_2") (pintype "passive"))
      (node (ref "D10") (pin "C") (pinfunction "C_C") (pintype "passive"))
      (node (ref "D8") (pin "A") (pinfunction "A_A") (pintype "passive"))
      (node (ref "IC2") (pin "1") (pinfunction "1.VCC_1") (pintype "power_in"))
      (node (ref "IC9") (pin "8") (pinfunction "V+_8") (pintype "power_in"))
      (node (ref "L5") (pin "2") (pinfunction "2_2") (pintype "passive"))
      (node (ref "OC1") (pin "1") (pinfunction "1_1") (pintype "passive"))
      (node (ref "R107") (pin "2") (pinfunction "2_2") (pintype "passive"))
      (node (ref "R133") (pin "2") (pinfunction "2_2") (pintype "passive"))
      (node (ref "R69") (pin "1") (pinfunction "1_1") (pintype "passive"))
      (node (ref "R88") (pin "2") (pinfunction "2_2") (pintype "passive"))
      (node (ref "R92") (pin "1") (pinfunction "1_1") (pintype "passive"))
      (node (ref "RL1") (pin "2") (pinfunction "2_2") (pintype "passive"))
    )
    (net (code "13") (name "BOOST_INP") (class "Default")
      (node (ref "C63") (pin "1") (pinfunction "1_1") (pintype "passive"))
      (node (ref "R91") (pin "1") (pinfunction "1_1") (pintype "passive"))
      (node (ref "U1") (pin "15") (pinfunction "PA5_15") (pintype "bidirectional"))
    )
    (net (code "14") (name "EARTH") (class "Default")
      (node (ref "C11") (pin "2") (pinfunction "2_2") (pintype "passive"))
      (node (ref "C25") (pin "1") (pinfunction "1_1") (pintype "passive"))
      (node (ref "C27") (pin "1") (pinfunction "1_1") (pintype "passive"))
      (node (ref "C35") (pin "2") (pinfunction "2_2") (pintype "passive"))
      (node (ref "C4") (pin "2") (pinfunction "2_2") (pintype "passive"))
      (node (ref "C5") (pin "2") (pinfunction "2_2") (pintype "passive"))
      (node (ref "C59") (pin "1") (pinfunction "1_1") (pintype "passive"))
      (node (ref "C7") (pin "2") (pinfunction "2_2") (pintype "passive"))
      (node (ref "C73") (pin "2") (pinfunction "2_2") (pintype "passive"))
      (node (ref "C74") (pin "P$2") (pinfunction "2_P$2") (pintype "passive"))
      (node (ref "C75") (pin "P$2") (pinfunction "2_P$2") (pintype "passive"))
      (node (ref "C87") (pin "P$2") (pinfunction "2_P$2") (pintype "passive"))
      (node (ref "C88") (pin "P$2") (pinfunction "2_P$2") (pintype "passive"))
      (node (ref "C89") (pin "1") (pinfunction "1_1") (pintype "passive"))
      (node (ref "C89") (pin "3") (pinfunction "1_3") (pintype "passive"))
      (node (ref "C90") (pin "2") (pinfunction "2_2") (pintype "passive"))
      (node (ref "C90") (pin "4") (pinfunction "2_4") (pintype "passive"))
      (node (ref "X1") (pin "3") (pinfunction "1_3") (pintype "passive"))
    )
    (net (code "15") (name "GND") (class "Default")
      (node (ref "B1") (pin "-") (pinfunction "-_-") (pintype "passive"))
      (node (ref "C10") (pin "-") (pinfunction "-_-") (pintype "passive"))
      (node (ref "C12") (pin "-") (pinfunction "-_-") (pintype "passive"))
      (node (ref "C13") (pin "-") (pinfunction "-_-") (pintype "passive"))
      (node (ref "C14") (pin "2") (pinfunction "2_2") (pintype "passive"))
      (node (ref "C15") (pin "2") (pinfunction "2_2") (pintype "passive"))
      (node (ref "C18") (pin "P$2") (pinfunction "2_P$2") (pintype "passive"))
      (node (ref "C29") (pin "1") (pinfunction "1_1") (pintype "passive"))
      (node (ref "C59") (pin "2") (pinfunction "2_2") (pintype "passive"))
      (node (ref "C6") (pin "2") (pinfunction "2_2") (pintype "passive"))
      (node (ref "C7") (pin "1") (pinfunction "1_1") (pintype "passive"))
      (node (ref "C76") (pin "2") (pinfunction "2_2") (pintype "passive"))
      (node (ref "C8") (pin "2") (pinfunction "2_2") (pintype "passive"))
      (node (ref "C82") (pin "2") (pinfunction "2_2") (pintype "passive"))
      (node (ref "C9") (pin "1") (pinfunction "1_1") (pintype "passive"))
      (node (ref "IC1") (pin "4") (pinfunction "GND_4") (pintype "power_in"))
      (node (ref "NTC2") (pin "2") (pinfunction "2_2") (pintype "passive"))
      (node (ref "OC1") (pin "3") (pinfunction "3_3") (pintype "passive"))
      (node (ref "OC2") (pin "3") (pinfunction "3_3") (pintype "passive"))
      (node (ref "R10") (pin "1") (pinfunction "1_1") (pintype "passive"))
      (node (ref "R118") (pin "1") (pinfunction "1_1") (pintype "passive"))
      (node (ref "R119") (pin "1") (pinfunction "1_1") (pintype "passive"))
      (node (ref "TRF1") (pin "14") (pinfunction "7_14") (pintype "passive"))
      (node (ref "TRF1") (pin "33") (pinfunction "7_33") (pintype "passive"))
      (node (ref "TRF1") (pin "48") (pinfunction "8_48") (pintype "passive"))
      (node (ref "TRF1") (pin "49") (pinfunction "7_49") (pintype "passive"))
      (node (ref "TRF1") (pin "6") (pinfunction "7_6") (pintype "passive"))
      (node (ref "Z1") (pin "1") (pinfunction "A_1") (pintype "passive"))
    )
    (net (code "16") (name "GNDA") (class "Default")
      (node (ref "C110") (pin "1") (pinfunction "1_1") (pintype "passive"))
      (node (ref "C2") (pin "1") (pinfunction "1_1") (pintype "passive"))
      (node (ref "C20") (pin "-") (pinfunction "-_-") (pintype "passive"))
      (node (ref "C22") (pin "P$1") (pinfunction "1_P$1") (pintype "passive"))
      (node (ref "C23") (pin "2") (pinfunction "2_2") (pintype "passive"))
      (node (ref "C26") (pin "2") (pinfunction "2_2") (pintype "passive"))
      (node (ref "C28") (pin "1") (pinfunction "1_1") (pintype "passive"))
      (node (ref "C30") (pin "1") (pinfunction "1_1") (pintype "passive"))
      (node (ref "C31") (pin "2") (pinfunction "2_2") (pintype "passive"))
      (node (ref "C32") (pin "2") (pinfunction "2_2") (pintype "passive"))
      (node (ref "C33") (pin "1") (pinfunction "1_1") (pintype "passive"))
      (node (ref "C34") (pin "1") (pinfunction "1_1") (pintype "passive"))
      (node (ref "C35") (pin "1") (pinfunction "1_1") (pintype "passive"))
      (node (ref "C36") (pin "2") (pinfunction "2_2") (pintype "passive"))
      (node (ref "C37") (pin "2") (pinfunction "2_2") (pintype "passive"))
      (node (ref "C38") (pin "2") (pinfunction "2_2") (pintype "passive"))
      (node (ref "C39") (pin "2") (pinfunction "2_2") (pintype "passive"))
      (node (ref "C40") (pin "-") (pinfunction "-_-") (pintype "passive"))
      (node (ref "C40") (pin "-1") (pinfunction "-_-1") (pintype "passive"))
      (node (ref "C41") (pin "2") (pinfunction "2_2") (pintype "passive"))
      (node (ref "C42") (pin "-") (pinfunction "-_-") (pintype "passive"))
      (node (ref "C43") (pin "1") (pinfunction "1_1") (pintype "passive"))
      (node (ref "C44") (pin "2") (pinfunction "2_2") (pintype "passive"))
      (node (ref "C45") (pin "2") (pinfunction "2_2") (pintype "passive"))
      (node (ref "C47") (pin "2") (pinfunction "2_2") (pintype "passive"))
      (node (ref "C48") (pin "2") (pinfunction "2_2") (pintype "passive"))
      (node (ref "C49") (pin "2") (pinfunction "2_2") (pintype "passive"))
      (node (ref "C51") (pin "2") (pinfunction "2_2") (pintype "passive"))
      (node (ref "C53") (pin "2") (pinfunction "2_2") (pintype "passive"))
      (node (ref "C54") (pin "2") (pinfunction "2_2") (pintype "passive"))
      (node (ref "C55") (pin "2") (pinfunction "2_2") (pintype "passive"))
      (node (ref "C57") (pin "2") (pinfunction "2_2") (pintype "passive"))
      (node (ref "C60") (pin "1") (pinfunction "1_1") (pintype "passive"))
      (node (ref "C61") (pin "2") (pinfunction "2_2") (pintype "passive"))
      (node (ref "C62") (pin "1") (pinfunction "1_1") (pintype "passive"))
      (node (ref "C63") (pin "2") (pinfunction "2_2") (pintype "passive"))
      (node (ref "C64") (pin "2") (pinfunction "2_2") (pintype "passive"))
      (node (ref "C65") (pin "1") (pinfunction "1_1") (pintype "passive"))
      (node (ref "C66") (pin "2") (pinfunction "2_2") (pintype "passive"))
      (node (ref "C67") (pin "2") (pinfunction "2_2") (pintype "passive"))
      (node (ref "C68") (pin "1") (pinfunction "1_1") (pintype "passive"))
      (node (ref "C69") (pin "1") (pinfunction "1_1") (pintype "passive"))
      (node (ref "C70") (pin "1") (pinfunction "1_1") (pintype "passive"))
      (node (ref "C72") (pin "1") (pinfunction "1_1") (pintype "passive"))
      (node (ref "C75") (pin "P$1") (pinfunction "1_P$1") (pintype "passive"))
      (node (ref "C78") (pin "2") (pinfunction "2_2") (pintype "passive"))
      (node (ref "C79") (pin "1") (pinfunction "1_1") (pintype "passive"))
      (node (ref "C87") (pin "P$1") (pinfunction "1_P$1") (pintype "passive"))
      (node (ref "C98") (pin "1") (pinfunction "1_1") (pintype "passive"))
      (node (ref "D12") (pin "A1") (pinfunction "A1_A1") (pintype "passive"))
      (node (ref "D13") (pin "1") (pinfunction "A_1") (pintype "passive"))
      (node (ref "D16") (pin "1") (pinfunction "A_1") (pintype "passive"))
      (node (ref "D18") (pin "A") (pinfunction "A_A") (pintype "passive"))
      (node (ref "HS2") (pin "1") (pinfunction "P$1_1") (pintype "power_in"))
      (node (ref "HS2") (pin "2") (pinfunction "P$1_2") (pintype "power_in"))
      (node (ref "IC2") (pin "5") (pinfunction "5.TRIG_5") (pintype "output"))
      (node (ref "IC2") (pin "7") (pinfunction "7.GND_7") (pintype "power_in"))
      (node (ref "IC4") (pin "1") (pinfunction "GND_1") (pintype "input"))
      (node (ref "IC5") (pin "4") (pinfunction "V-_4") (pintype "power_in"))
      (node (ref "IC6") (pin "A") (pinfunction "1_A") (pintype "passive"))
      (node (ref "IC9") (pin "4") (pinfunction "V-_4") (pintype "power_in"))
      (node (ref "L2") (pin "1") (pinfunction "1.GND_1") (pintype "passive"))
      (node (ref "L2") (pin "4") (pinfunction "4.GND_4") (pintype "passive"))
      (node (ref "NTC3") (pin "2") (pinfunction "2_2") (pintype "passive"))
      (node (ref "PROG1") (pin "3") (pinfunction "GND_3") (pintype "passive"))
      (node (ref "Q2") (pin "S") (pinfunction "S_S") (pintype "passive"))
      (node (ref "R102") (pin "1") (pinfunction "1_1") (pintype "passive"))
      (node (ref "R122") (pin "1") (pinfunction "1_1") (pintype "passive"))
      (node (ref "R125") (pin "1") (pinfunction "1_1") (pintype "passive"))
      (node (ref "R135") (pin "1") (pinfunction "1_1") (pintype "passive"))
      (node (ref "R25") (pin "2") (pinfunction "2_2") (pintype "passive"))
      (node (ref "R26") (pin "2") (pinfunction "2_2") (pintype "passive"))
      (node (ref "R38") (pin "2") (pinfunction "2_2") (pintype "passive"))
      (node (ref "R39") (pin "2") (pinfunction "2_2") (pintype "passive"))
      (node (ref "R40") (pin "2") (pinfunction "2_2") (pintype "passive"))
      (node (ref "R41") (pin "2") (pinfunction "2_2") (pintype "passive"))
      (node (ref "R42") (pin "2") (pinfunction "2_2") (pintype "passive"))
      (node (ref "R43") (pin "2") (pinfunction "2_2") (pintype "passive"))
      (node (ref "R44") (pin "2") (pinfunction "2_2") (pintype "passive"))
      (node (ref "R47") (pin "2") (pinfunction "2_2") (pintype "passive"))
      (node (ref "R48") (pin "2") (pinfunction "2_2") (pintype "passive"))
      (node (ref "R51") (pin "2") (pinfunction "2_2") (pintype "passive"))
      (node (ref "R56") (pin "1") (pinfunction "1_1") (pintype "passive"))
      (node (ref "R58") (pin "2") (pinfunction "2_2") (pintype "passive"))
      (node (ref "R64") (pin "1") (pinfunction "1_1") (pintype "passive"))
      (node (ref "R65") (pin "1") (pinfunction "1_1") (pintype "passive"))
      (node (ref "R68") (pin "1") (pinfunction "1_1") (pintype "passive"))
      (node (ref "R75") (pin "1") (pinfunction "1_1") (pintype "passive"))
      (node (ref "R81") (pin "2") (pinfunction "2_2") (pintype "passive"))
      (node (ref "R82") (pin "2") (pinfunction "2_2") (pintype "passive"))
      (node (ref "R87") (pin "1") (pinfunction "1_1") (pintype "passive"))
      (node (ref "R90") (pin "1") (pinfunction "1_1") (pintype "passive"))
      (node (ref "R99") (pin "1") (pinfunction "1_1") (pintype "passive"))
      (node (ref "T2") (pin "E") (pinfunction "E_E") (pintype "passive"))
      (node (ref "T5") (pin "E") (pinfunction "E_E") (pintype "passive"))
      (node (ref "T6") (pin "E") (pinfunction "E_E") (pintype "passive"))
      (node (ref "TRF1") (pin "24") (pinfunction "10_24") (pintype "passive"))
      (node (ref "TRF1") (pin "27") (pinfunction "10_27") (pintype "passive"))
      (node (ref "TRF1") (pin "40") (pinfunction "9_40") (pintype "passive"))
      (node (ref "TRF1") (pin "41") (pinfunction "10_41") (pintype "passive"))
      (node (ref "TRF1") (pin "6.1") (pinfunction "9_6.1") (pintype "passive"))
      (node (ref "TRF1") (pin "6.2") (pinfunction "9_6.2") (pintype "passive"))
      (node (ref "TRF1") (pin "6.5") (pinfunction "9_6.5") (pintype "passive"))
      (node (ref "TRF1") (pin "7") (pinfunction "10_7") (pintype "passive"))
      (node (ref "TVS1") (pin "A") (pinfunction "1_A") (pintype "passive"))
      (node (ref "U1") (pin "23") (pinfunction "VSS.._23") (pintype "bidirectional"))
      (node (ref "U1") (pin "35") (pinfunction "VSS_35") (pintype "bidirectional"))
      (node (ref "U1") (pin "47") (pinfunction "VSS._47") (pintype "bidirectional"))
      (node (ref "U1") (pin "8") (pinfunction "VSSA_8") (pintype "bidirectional"))
      (node (ref "U2") (pin "2") (pinfunction "GND_2") (pintype "bidirectional"))
      (node (ref "X2") (pin "GND") (pinfunction "GND_GND") (pintype "bidirectional"))
      (node (ref "X2") (pin "SHLD1") (pinfunction "1_SHLD1") (pintype "bidirectional"))
      (node (ref "X2") (pin "SHLD2") (pinfunction "2_SHLD2") (pintype "bidirectional"))
      (node (ref "X4") (pin "1") (pinfunction "1_1") (pintype "passive"))
      (node (ref "Y1") (pin "2") (pinfunction "2.GND_2") (pintype "bidirectional"))
      (node (ref "Y1") (pin "3") (pinfunction "3_3") (pintype "bidirectional"))
      (node (ref "Z3") (pin "1") (pinfunction "A_1") (pintype "passive"))
      (node (ref "Z4") (pin "1") (pinfunction "A_1") (pintype "passive"))
      (node (ref "Z6") (pin "1") (pinfunction "A_1") (pintype "passive"))
    )
    (net (code "17") (name "GNDINT") (class "Default")
      (node (ref "C46") (pin "1") (pinfunction "1_1") (pintype "passive"))
      (node (ref "C71") (pin "2") (pinfunction "2_2") (pintype "passive"))
      (node (ref "C84") (pin "-") (pinfunction "-_-") (pintype "passive"))
      (node (ref "C84_X") (pin "-") (pinfunction "-_-") (pintype "passive"))
      (node (ref "C85") (pin "2") (pinfunction "2_2") (pintype "passive"))
      (node (ref "C86") (pin "2") (pinfunction "2_2") (pintype "passive"))
      (node (ref "IC3") (pin "6") (pinfunction "GND_6") (pintype "power_in"))
      (node (ref "IC8") (pin "S") (pinfunction "S123_S") (pintype "passive"))
      (node (ref "IC8") (pin "S1") (pinfunction "S123_S1") (pintype "passive"))
      (node (ref "IC8") (pin "S2") (pinfunction "S123_S2") (pintype "passive"))
      (node (ref "R114") (pin "2") (pinfunction "2_2") (pintype "passive"))
      (node (ref "R116") (pin "1") (pinfunction "1_1") (pintype "passive"))
      (node (ref "R65") (pin "2") (pinfunction "2_2") (pintype "passive"))
      (node (ref "R66") (pin "2") (pinfunction "2_2") (pintype "passive"))
      (node (ref "R67") (pin "2") (pinfunction "2_2") (pintype "passive"))
      (node (ref "R80") (pin "1") (pinfunction "1_1") (pintype "passive"))
      (node (ref "T7") (pin "E") (pinfunction "E_E") (pintype "passive"))
      (node (ref "T9") (pin "E") (pinfunction "E_E") (pintype "passive"))
      (node (ref "Z7") (pin "1") (pinfunction "A_1") (pintype "passive"))
      (node (ref "Z8") (pin "1") (pinfunction "A_1") (pintype "passive"))
    )
    (net (code "18") (name "GNDIO") (class "Default")
      (node (ref "D15") (pin "C") (pinfunction "C_C") (pintype "passive"))
      (node (ref "IC8") (pin "D") (pinfunction "D5678_D") (pintype "passive"))
      (node (ref "IC8") (pin "D1") (pinfunction "D5678_D1") (pintype "passive"))
      (node (ref "IC8") (pin "D2") (pinfunction "D5678_D2") (pintype "passive"))
      (node (ref "IC8") (pin "D3") (pinfunction "D5678_D3") (pintype "passive"))
      (node (ref "IC8") (pin "P$1") (pinfunction "D5678_P$1") (pintype "passive"))
      (node (ref "IC8") (pin "P$2") (pinfunction "D5678_P$2") (pintype "passive"))
      (node (ref "IC8") (pin "P$3") (pinfunction "D5678_P$3") (pintype "passive"))
      (node (ref "R57") (pin "1") (pinfunction "1_1") (pintype "passive"))
      (node (ref "T10") (pin "E") (pinfunction "E_E") (pintype "passive"))
      (node (ref "X3") (pin "2") (pinfunction "1_2") (pintype "passive"))
    )
    (net (code "19") (name "I_OUT_ADC") (class "Default")
      (node (ref "C62") (pin "2") (pinfunction "2_2") (pintype "passive"))
      (node (ref "R83") (pin "2") (pinfunction "2_2") (pintype "passive"))
      (node (ref "U1") (pin "17") (pinfunction "PA7_17") (pintype "bidirectional"))
    )
    (net (code "20") (name "I_PWM") (class "Default")
      (node (ref "R55") (pin "2") (pinfunction "2_2") (pintype "passive"))
      (node (ref "U1") (pin "18") (pinfunction "PB0_18") (pintype "bidirectional"))
    )
    (net (code "21") (name "JTDO") (class "Default")
      (node (ref "PROG1") (pin "6") (pinfunction "PRG_SWO_6") (pintype "passive"))
      (node (ref "U1") (pin "39") (pinfunction "PB3_39") (pintype "bidirectional"))
    )
    (net (code "22") (name "LED_B") (class "Default")
      (node (ref "R52") (pin "1") (pinfunction "1_1") (pintype "passive"))
      (node (ref "U1") (pin "41") (pinfunction "PB5_41") (pintype "bidirectional"))
    )
    (net (code "23") (name "LED_G") (class "Default")
      (node (ref "R53") (pin "1") (pinfunction "1_1") (pintype "passive"))
      (node (ref "U1") (pin "40") (pinfunction "PB4_40") (pintype "bidirectional"))
    )
    (net (code "24") (name "LED_R") (class "Default")
      (node (ref "R49") (pin "1") (pinfunction "1_1") (pintype "passive"))
      (node (ref "U1") (pin "42") (pinfunction "PB6_42") (pintype "bidirectional"))
    )
    (net (code "25") (name "NRST") (class "Default")
      (node (ref "C30") (pin "2") (pinfunction "2_2") (pintype "passive"))
      (node (ref "PROG1") (pin "5") (pinfunction "NRST_5") (pintype "passive"))
      (node (ref "R46") (pin "2") (pinfunction "2_2") (pintype "passive"))
      (node (ref "U1") (pin "7") (pinfunction "NRST_7") (pintype "bidirectional"))
    )
    (net (code "26") (name "Net-(B1-PadAC1)") (class "Default")
      (node (ref "B1") (pin "AC1") (pinfunction "AC1_AC1") (pintype "passive"))
      (node (ref "C4") (pin "1") (pinfunction "1_1") (pintype "passive"))
      (node (ref "C83") (pin "2") (pinfunction "2_2") (pintype "passive"))
      (node (ref "C83") (pin "4") (pinfunction "2_4") (pintype "passive"))
      (node (ref "L1") (pin "4") (pinfunction "4_4") (pintype "passive"))
      (node (ref "L1") (pin "7") (pinfunction "4_7") (pintype "passive"))
    )
    (net (code "27") (name "Net-(B1-PadAC2)") (class "Default")
      (node (ref "B1") (pin "AC2") (pinfunction "AC2_AC2") (pintype "passive"))
      (node (ref "C5") (pin "1") (pinfunction "1_1") (pintype "passive"))
      (node (ref "C83") (pin "1") (pinfunction "1_1") (pintype "passive"))
      (node (ref "C83") (pin "3") (pinfunction "1_3") (pintype "passive"))
      (node (ref "L1") (pin "2") (pinfunction "2_2") (pintype "passive"))
      (node (ref "L1") (pin "6") (pinfunction "2_6") (pintype "passive"))
    )
    (net (code "28") (name "Net-(C1-Pad2)") (class "Default")
      (node (ref "C1") (pin "2") (pinfunction "2_2") (pintype "passive"))
      (node (ref "R124") (pin "1") (pinfunction "1_1") (pintype "passive"))
    )
    (net (code "29") (name "Net-(C3-1-Pad3)") (class "Default")
      (node (ref "C3") (pin "1") (pinfunction "1_1") (pintype "passive"))
      (node (ref "C3") (pin "3") (pinfunction "1_3") (pintype "passive"))
      (node (ref "C3") (pin "5") (pinfunction "1_5") (pintype "passive"))
      (node (ref "L3") (pin "1") (pinfunction "1_1") (pintype "passive"))
      (node (ref "NTC1") (pin "P$1") (pinfunction "1_P$1") (pintype "passive"))
      (node (ref "NTC1") (pin "P$4") (pinfunction "1_P$4") (pintype "passive"))
      (node (ref "R4") (pin "2") (pinfunction "2_2") (pintype "passive"))
      (node (ref "VR1") (pin "2") (pinfunction "2_2") (pintype "passive"))
    )
    (net (code "30") (name "Net-(C3-2-Pad4)") (class "Default")
      (node (ref "C3") (pin "2") (pinfunction "2_2") (pintype "passive"))
      (node (ref "C3") (pin "4") (pinfunction "2_4") (pintype "passive"))
      (node (ref "C3") (pin "6") (pinfunction "2_6") (pintype "passive"))
      (node (ref "F1") (pin "2") (pinfunction "2_2") (pintype "passive"))
      (node (ref "L3") (pin "2") (pinfunction "2_2") (pintype "passive"))
      (node (ref "R2") (pin "1") (pinfunction "1_1") (pintype "passive"))
      (node (ref "VR1") (pin "1") (pinfunction "1_1") (pintype "passive"))
    )
    (net (code "31") (name "Net-(C16-Pad1)") (class "Default")
      (node (ref "C16") (pin "1") (pinfunction "1_1") (pintype "passive"))
      (node (ref "D1") (pin "C") (pinfunction "C_C") (pintype "passive"))
      (node (ref "R13") (pin "2") (pinfunction "2_2") (pintype "passive"))
    )
    (net (code "32") (name "Net-(C16-Pad2)") (class "Default")
      (node (ref "C16") (pin "2") (pinfunction "2_2") (pintype "passive"))
      (node (ref "R19") (pin "1") (pinfunction "1_1") (pintype "passive"))
    )
    (net (code "33") (name "Net-(C17-1-Pad3)") (class "Default")
      (node (ref "C17") (pin "1") (pinfunction "1_1") (pintype "passive"))
      (node (ref "C17") (pin "3") (pinfunction "1_3") (pintype "passive"))
      (node (ref "D4") (pin "A") (pinfunction "A_A") (pintype "passive"))
      (node (ref "Q1") (pin "D") (pinfunction "D_D") (pintype "passive"))
      (node (ref "TRF1") (pin "55") (pinfunction "1_55") (pintype "passive"))
      (node (ref "TRF1") (pin "56") (pinfunction "1_56") (pintype "passive"))
      (node (ref "TRF1") (pin "57") (pinfunction "1_57") (pintype "passive"))
      (node (ref "TRF1") (pin "58") (pinfunction "1_58") (pintype "passive"))
    )
    (net (code "34") (name "Net-(C17-2-Pad4)") (class "Default")
      (node (ref "C17") (pin "2") (pinfunction "2_2") (pintype "passive"))
      (node (ref "C17") (pin "4") (pinfunction "2_4") (pintype "passive"))
      (node (ref "R31") (pin "1") (pinfunction "1_1") (pintype "passive"))
    )
    (net (code "35") (name "Net-(C19-Pad1)") (class "Default")
      (node (ref "C19") (pin "1") (pinfunction "1_1") (pintype "passive"))
      (node (ref "R35") (pin "1") (pinfunction "1_1") (pintype "passive"))
    )
    (net (code "36") (name "Net-(C19-Pad2)") (class "Default")
      (node (ref "C19") (pin "2") (pinfunction "2_2") (pintype "passive"))
      (node (ref "D6") (pin "A") (pinfunction "A_A") (pintype "passive"))
      (node (ref "FB3") (pin "1") (pinfunction "1_1") (pintype "passive"))
    )
    (net (code "37") (name "Net-(C21-1-Pad3)") (class "Default")
      (node (ref "C21") (pin "1") (pinfunction "1_1") (pintype "passive"))
      (node (ref "C21") (pin "3") (pinfunction "1_3") (pintype "passive"))
      (node (ref "R25") (pin "1") (pinfunction "1_1") (pintype "passive"))
      (node (ref "R26") (pin "1") (pinfunction "1_1") (pintype "passive"))
      (node (ref "R39") (pin "1") (pinfunction "1_1") (pintype "passive"))
      (node (ref "R40") (pin "1") (pinfunction "1_1") (pintype "passive"))
      (node (ref "R41") (pin "1") (pinfunction "1_1") (pintype "passive"))
      (node (ref "R42") (pin "1") (pinfunction "1_1") (pintype "passive"))
      (node (ref "R43") (pin "1") (pinfunction "1_1") (pintype "passive"))
    )
    (net (code "38") (name "Net-(C43-Pad2)") (class "Default")
      (node (ref "C43") (pin "2") (pinfunction "2_2") (pintype "passive"))
      (node (ref "R60") (pin "2") (pinfunction "2_2") (pintype "passive"))
      (node (ref "R62") (pin "2") (pinfunction "2_2") (pintype "passive"))
    )
    (net (code "39") (name "Net-(C52-Pad1)") (class "Default")
      (node (ref "C52") (pin "1") (pinfunction "1_1") (pintype "passive"))
      (node (ref "R70") (pin "1") (pinfunction "1_1") (pintype "passive"))
    )
    (net (code "40") (name "Net-(C56-Pad1)") (class "Default")
      (node (ref "C56") (pin "1") (pinfunction "1_1") (pintype "passive"))
      (node (ref "R76") (pin "1") (pinfunction "1_1") (pintype "passive"))
    )
    (net (code "41") (name "Net-(C60-Pad2)") (class "Default")
      (node (ref "C60") (pin "2") (pinfunction "2_2") (pintype "passive"))
      (node (ref "R82") (pin "1") (pinfunction "1_1") (pintype "passive"))
      (node (ref "R84") (pin "2") (pinfunction "2_2") (pintype "passive"))
      (node (ref "T4") (pin "B") (pinfunction "B_B") (pintype "passive"))
    )
    (net (code "42") (name "Net-(C68-Pad2)") (class "Default")
      (node (ref "C68") (pin "2") (pinfunction "2_2") (pintype "passive"))
      (node (ref "R103") (pin "1") (pinfunction "1_1") (pintype "passive"))
      (node (ref "R104") (pin "2") (pinfunction "2_2") (pintype "passive"))
    )
    (net (code "43") (name "Net-(C77-Pad1)") (class "Default")
      (node (ref "C77") (pin "1") (pinfunction "1_1") (pintype "passive"))
      (node (ref "R194") (pin "2") (pinfunction "2_2") (pintype "passive"))
    )
    (net (code "44") (name "Net-(C80-Pad2)") (class "Default")
      (node (ref "C80") (pin "2") (pinfunction "2_2") (pintype "passive"))
      (node (ref "C91") (pin "2") (pinfunction "2_2") (pintype "passive"))
    )
    (net (code "45") (name "Net-(C89-2-Pad4)") (class "Default")
      (node (ref "C89") (pin "2") (pinfunction "2_2") (pintype "passive"))
      (node (ref "C89") (pin "4") (pinfunction "2_4") (pintype "passive"))
      (node (ref "L1") (pin "3") (pinfunction "3_3") (pintype "passive"))
      (node (ref "L1") (pin "8") (pinfunction "3_8") (pintype "passive"))
      (node (ref "L3") (pin "4") (pinfunction "4_4") (pintype "passive"))
    )
    (net (code "46") (name "Net-(C90-1-Pad3)") (class "Default")
      (node (ref "C90") (pin "1") (pinfunction "1_1") (pintype "passive"))
      (node (ref "C90") (pin "3") (pinfunction "1_3") (pintype "passive"))
      (node (ref "L1") (pin "1") (pinfunction "1_1") (pintype "passive"))
      (node (ref "L1") (pin "5") (pinfunction "1_5") (pintype "passive"))
      (node (ref "L3") (pin "3") (pinfunction "3_3") (pintype "passive"))
    )
    (net (code "47") (name "Net-(D1-PadA)") (class "Default")
      (node (ref "D1") (pin "A") (pinfunction "A_A") (pintype "passive"))
      (node (ref "FB2") (pin "2") (pinfunction "2_2") (pintype "passive"))
      (node (ref "R19") (pin "2") (pinfunction "2_2") (pintype "passive"))
    )
    (net (code "48") (name "Net-(D2-PadC)") (class "Default")
      (node (ref "D2") (pin "C") (pinfunction "C_C") (pintype "passive"))
      (node (ref "R17") (pin "1") (pinfunction "1_1") (pintype "passive"))
      (node (ref "R18") (pin "1") (pinfunction "1_1") (pintype "passive"))
    )
    (net (code "49") (name "Net-(D3-PadC)") (class "Default")
      (node (ref "D3") (pin "C") (pinfunction "C_C") (pintype "passive"))
      (node (ref "R23") (pin "1") (pinfunction "1_1") (pintype "passive"))
      (node (ref "R24") (pin "1") (pinfunction "1_1") (pintype "passive"))
    )
    (net (code "50") (name "Net-(D4-PadC)") (class "Default")
      (node (ref "D4") (pin "C") (pinfunction "C_C") (pintype "passive"))
      (node (ref "R17") (pin "2") (pinfunction "2_2") (pintype "passive"))
      (node (ref "R18") (pin "2") (pinfunction "2_2") (pintype "passive"))
      (node (ref "R23") (pin "2") (pinfunction "2_2") (pintype "passive"))
      (node (ref "R24") (pin "2") (pinfunction "2_2") (pintype "passive"))
    )
    (net (code "51") (name "Net-(D5-PadA)") (class "Default")
      (node (ref "D5") (pin "A") (pinfunction "A_A") (pintype "passive"))
      (node (ref "Q1") (pin "G") (pinfunction "G_G") (pintype "passive"))
      (node (ref "R14") (pin "1") (pinfunction "1_1") (pintype "passive"))
      (node (ref "R21") (pin "2") (pinfunction "2_2") (pintype "passive"))
    )
    (net (code "52") (name "Net-(D5-PadC)") (class "Default")
      (node (ref "D5") (pin "C") (pinfunction "C_C") (pintype "passive"))
      (node (ref "R14") (pin "2") (pinfunction "2_2") (pintype "passive"))
      (node (ref "R15") (pin "1") (pinfunction "1_1") (pintype "passive"))
    )
    (net (code "53") (name "Net-(D9-A1)") (class "Default")
      (node (ref "C64") (pin "1") (pinfunction "1_1") (pintype "passive"))
      (node (ref "D9") (pin "1") (pinfunction "A1_1") (pintype "passive"))
      (node (ref "D9") (pin "2") (pinfunction "A2_2") (pintype "passive"))
      (node (ref "RF1") (pin "1") (pinfunction "1_1") (pintype "passive"))
      (node (ref "TVS1") (pin "C") (pinfunction "2_C") (pintype "passive"))
    )
    (net (code "54") (name "Net-(D10-PadA)") (class "Default")
      (node (ref "D10") (pin "A") (pinfunction "A_A") (pintype "passive"))
      (node (ref "RL1") (pin "1") (pinfunction "1_1") (pintype "passive"))
      (node (ref "T5") (pin "C") (pinfunction "C_C") (pintype "passive"))
    )
    (net (code "55") (name "Net-(D11-PadA)") (class "Default")
      (node (ref "D11") (pin "A") (pinfunction "A_A") (pintype "passive"))
      (node (ref "R93") (pin "1") (pinfunction "1_1") (pintype "passive"))
    )
    (net (code "56") (name "Net-(D15-PadA)") (class "Default")
      (node (ref "D15") (pin "A") (pinfunction "A_A") (pintype "passive"))
      (node (ref "R117") (pin "2") (pinfunction "2_2") (pintype "passive"))
      (node (ref "T10") (pin "B") (pinfunction "B_B") (pintype "passive"))
    )
    (net (code "57") (name "Net-(D16-AC)") (class "Default")
      (node (ref "D16") (pin "3") (pinfunction "AC_3") (pintype "passive"))
      (node (ref "R124") (pin "2") (pinfunction "2_2") (pintype "passive"))
      (node (ref "R125") (pin "2") (pinfunction "2_2") (pintype "passive"))
    )
    (net (code "58") (name "Net-(D16-C)") (class "Default")
      (node (ref "C2") (pin "2") (pinfunction "2_2") (pintype "passive"))
      (node (ref "D16") (pin "2") (pinfunction "C_2") (pintype "passive"))
      (node (ref "R123") (pin "1") (pinfunction "1_1") (pintype "passive"))
    )
    (net (code "59") (name "Net-(F1-Pad1)") (class "Default")
      (node (ref "F1") (pin "1") (pinfunction "1_1") (pintype "passive"))
      (node (ref "X1") (pin "1") (pinfunction "1_1") (pintype "passive"))
    )
    (net (code "60") (name "Net-(FB2-Pad1)") (class "Default")
      (node (ref "FB2") (pin "1") (pinfunction "1_1") (pintype "passive"))
      (node (ref "TRF1") (pin "15") (pinfunction "6_15") (pintype "passive"))
      (node (ref "TRF1") (pin "34") (pinfunction "6_34") (pintype "passive"))
      (node (ref "TRF1") (pin "5") (pinfunction "6_5") (pintype "passive"))
      (node (ref "TRF1") (pin "50") (pinfunction "6_50") (pintype "passive"))
    )
    (net (code "61") (name "Net-(FB3-Pad2)") (class "Default")
      (node (ref "FB3") (pin "2") (pinfunction "2_2") (pintype "passive"))
      (node (ref "TRF1") (pin "23") (pinfunction "11_23") (pintype "passive"))
      (node (ref "TRF1") (pin "28") (pinfunction "11_28") (pintype "passive"))
      (node (ref "TRF1") (pin "42") (pinfunction "11_42") (pintype "passive"))
      (node (ref "TRF1") (pin "8") (pinfunction "11_8") (pintype "passive"))
    )
    (net (code "62") (name "Net-(IC1-CS)") (class "Default")
      (node (ref "C9") (pin "2") (pinfunction "2_2") (pintype "passive"))
      (node (ref "IC1") (pin "3") (pinfunction "CS_3") (pintype "input"))
      (node (ref "R6") (pin "1") (pinfunction "1_1") (pintype "passive"))
    )
    (net (code "63") (name "Net-(IC1-DRV)") (class "Default")
      (node (ref "IC1") (pin "5") (pinfunction "DRV_5") (pintype "output"))
      (node (ref "R15") (pin "2") (pinfunction "2_2") (pintype "passive"))
    )
    (net (code "64") (name "Net-(IC1-FAULT)") (class "Default")
      (node (ref "C6") (pin "1") (pinfunction "1_1") (pintype "passive"))
      (node (ref "IC1") (pin "1") (pinfunction "FAULT_1") (pintype "power_in"))
      (node (ref "R111") (pin "1") (pinfunction "1_1") (pintype "passive"))
      (node (ref "R37") (pin "1") (pinfunction "1_1") (pintype "passive"))
    )
    (net (code "65") (name "Net-(IC1-FB)") (class "Default")
      (node (ref "C8") (pin "1") (pinfunction "1_1") (pintype "passive"))
      (node (ref "IC1") (pin "2") (pinfunction "FB_2") (pintype "input"))
      (node (ref "OC1") (pin "4") (pinfunction "4_4") (pintype "passive"))
      (node (ref "OC2") (pin "4") (pinfunction "4_4") (pintype "passive"))
    )
    (net (code "66") (name "Net-(IC1-HV)") (class "Default")
      (node (ref "IC1") (pin "8") (pinfunction "HV_8") (pintype "input"))
      (node (ref "R12") (pin "2") (pinfunction "2_2") (pintype "passive"))
    )
    (net (code "67") (name "Net-(IC1-VCC)") (class "Default")
      (node (ref "C14") (pin "1") (pinfunction "1_1") (pintype "passive"))
      (node (ref "C15") (pin "1") (pinfunction "1_1") (pintype "passive"))
      (node (ref "FB1") (pin "2") (pinfunction "2_2") (pintype "passive"))
      (node (ref "IC1") (pin "6") (pinfunction "VCC_6") (pintype "input"))
    )
    (net (code "68") (name "Net-(IC2-2.MIN_TOFF)") (class "Default")
      (node (ref "IC2") (pin "2") (pinfunction "2.MIN_TOFF_2") (pintype "input"))
      (node (ref "R48") (pin "1") (pinfunction "1_1") (pintype "passive"))
    )
    (net (code "69") (name "Net-(IC2-3.MIN_TON)") (class "Default")
      (node (ref "IC2") (pin "3") (pinfunction "3.MIN_TON_3") (pintype "input"))
      (node (ref "R47") (pin "1") (pinfunction "1_1") (pintype "passive"))
    )
    (net (code "70") (name "Net-(IC2-8.DRV)") (class "Default")
      (node (ref "IC2") (pin "8") (pinfunction "8.DRV_8") (pintype "input"))
      (node (ref "R36") (pin "1") (pinfunction "1_1") (pintype "passive"))
    )
    (net (code "71") (name "Net-(IC3-CC+)") (class "Default")
      (node (ref "C91") (pin "1") (pinfunction "1_1") (pintype "passive"))
      (node (ref "IC3") (pin "3") (pinfunction "CC+_3") (pintype "input"))
      (node (ref "R62") (pin "1") (pinfunction "1_1") (pintype "passive"))
      (node (ref "R63") (pin "2") (pinfunction "2_2") (pintype "passive"))
    )
    (net (code "72") (name "Net-(IC3-CC-)") (class "Default")
      (node (ref "C80") (pin "1") (pinfunction "1_1") (pintype "passive"))
      (node (ref "IC3") (pin "2") (pinfunction "CC-_2") (pintype "input"))
      (node (ref "R66") (pin "1") (pinfunction "1_1") (pintype "passive"))
      (node (ref "R70") (pin "2") (pinfunction "2_2") (pintype "passive"))
    )
    (net (code "73") (name "Net-(IC3-CV-)") (class "Default")
      (node (ref "IC3") (pin "4") (pinfunction "CV-_4") (pintype "input"))
      (node (ref "R76") (pin "2") (pinfunction "2_2") (pintype "passive"))
      (node (ref "R79") (pin "1") (pinfunction "1_1") (pintype "passive"))
      (node (ref "R80") (pin "2") (pinfunction "2_2") (pintype "passive"))
    )
    (net (code "74") (name "Net-(IC3-OUT)") (class "Default")
      (node (ref "C52") (pin "2") (pinfunction "2_2") (pintype "passive"))
      (node (ref "C56") (pin "2") (pinfunction "2_2") (pintype "passive"))
      (node (ref "IC3") (pin "7") (pinfunction "OUT_7") (pintype "output"))
      (node (ref "R74") (pin "1") (pinfunction "1_1") (pintype "passive"))
    )
    (net (code "75") (name "Net-(IC3-VCC)") (class "Default")
      (node (ref "C46") (pin "2") (pinfunction "2_2") (pintype "passive"))
      (node (ref "IC3") (pin "8") (pinfunction "VCC_8") (pintype "power_in"))
      (node (ref "R69") (pin "2") (pinfunction "2_2") (pintype "passive"))
    )
    (net (code "76") (name "Net-(IC5A--IN)") (class "Default")
      (node (ref "C58") (pin "1") (pinfunction "1_1") (pintype "passive"))
      (node (ref "IC5") (pin "2") (pinfunction "-IN_2") (pintype "input"))
      (node (ref "R75") (pin "2") (pinfunction "2_2") (pintype "passive"))
      (node (ref "R77") (pin "1") (pinfunction "1_1") (pintype "passive"))
    )
    (net (code "77") (name "Net-(IC5A-OUT)") (class "Default")
      (node (ref "C58") (pin "2") (pinfunction "2_2") (pintype "passive"))
      (node (ref "IC5") (pin "1") (pinfunction "OUT_1") (pintype "output"))
      (node (ref "R77") (pin "2") (pinfunction "2_2") (pintype "passive"))
      (node (ref "R83") (pin "1") (pinfunction "1_1") (pintype "passive"))
    )
    (net (code "78") (name "Net-(IC5B-+IN)") (class "Default")
      (node (ref "C81") (pin "2") (pinfunction "2_2") (pintype "passive"))
      (node (ref "IC5") (pin "5") (pinfunction "+IN_5") (pintype "input"))
      (node (ref "R5") (pin "1") (pinfunction "1_1") (pintype "passive"))
      (node (ref "R67") (pin "1") (pinfunction "1_1") (pintype "passive"))
    )
    (net (code "79") (name "Net-(IC5B--IN)") (class "Default")
      (node (ref "C50") (pin "1") (pinfunction "1_1") (pintype "passive"))
      (node (ref "C81") (pin "1") (pinfunction "1_1") (pintype "passive"))
      (node (ref "IC5") (pin "6") (pinfunction "-IN_6") (pintype "input"))
      (node (ref "R68") (pin "2") (pinfunction "2_2") (pintype "passive"))
      (node (ref "R71") (pin "1") (pinfunction "1_1") (pintype "passive"))
    )
    (net (code "80") (name "Net-(IC6-2)") (class "Default")
      (node (ref "IC6") (pin "R") (pinfunction "2_R") (pintype "passive"))
      (node (ref "R89") (pin "1") (pinfunction "1_1") (pintype "passive"))
      (node (ref "R90") (pin "2") (pinfunction "2_2") (pintype "passive"))
    )
    (net (code "81") (name "Net-(IC6-3)") (class "Default")
      (node (ref "C65") (pin "2") (pinfunction "2_2") (pintype "passive"))
      (node (ref "IC6") (pin "C") (pinfunction "3_C") (pintype "passive"))
      (node (ref "IC9") (pin "3") (pinfunction "+IN_3") (pintype "input"))
      (node (ref "R88") (pin "1") (pinfunction "1_1") (pintype "passive"))
      (node (ref "R89") (pin "2") (pinfunction "2_2") (pintype "passive"))
    )
    (net (code "82") (name "Net-(IC8-G4)") (class "Default")
      (node (ref "IC8") (pin "GATE") (pinfunction "G4_GATE") (pintype "passive"))
      (node (ref "R107") (pin "1") (pinfunction "1_1") (pintype "passive"))
      (node (ref "R116") (pin "2") (pinfunction "2_2") (pintype "passive"))
      (node (ref "T7") (pin "C") (pinfunction "C_C") (pintype "passive"))
      (node (ref "T9") (pin "C") (pinfunction "C_C") (pintype "passive"))
      (node (ref "Z8") (pin "3") (pinfunction "C_3") (pintype "passive"))
    )
    (net (code "83") (name "Net-(IC9A--IN)") (class "Default")
      (node (ref "IC9") (pin "1") (pinfunction "OUT_1") (pintype "output"))
      (node (ref "IC9") (pin "2") (pinfunction "-IN_2") (pintype "input"))
      (node (ref "R101") (pin "2") (pinfunction "2_2") (pintype "passive"))
      (node (ref "R98") (pin "2") (pinfunction "2_2") (pintype "passive"))
    )
    (net (code "84") (name "Net-(IC9B-+IN)") (class "Default")
      (node (ref "D12") (pin "A") (pinfunction "A_A") (pintype "passive"))
      (node (ref "IC9") (pin "5") (pinfunction "+IN_5") (pintype "input"))
      (node (ref "R105") (pin "1") (pinfunction "1_1") (pintype "passive"))
      (node (ref "R94") (pin "2") (pinfunction "2_2") (pintype "passive"))
      (node (ref "R98") (pin "1") (pinfunction "1_1") (pintype "passive"))
    )
    (net (code "85") (name "Net-(IC9B--IN)") (class "Default")
      (node (ref "IC9") (pin "6") (pinfunction "-IN_6") (pintype "input"))
      (node (ref "R101") (pin "1") (pinfunction "1_1") (pintype "passive"))
      (node (ref "R102") (pin "2") (pinfunction "2_2") (pintype "passive"))
      (node (ref "R106") (pin "1") (pinfunction "1_1") (pintype "passive"))
    )
    (net (code "86") (name "Net-(IC9B-OUT)") (class "Default")
      (node (ref "IC9") (pin "7") (pinfunction "OUT_7") (pintype "output"))
      (node (ref "R105") (pin "2") (pinfunction "2_2") (pintype "passive"))
      (node (ref "R106") (pin "2") (pinfunction "2_2") (pintype "passive"))
      (node (ref "R108") (pin "1") (pinfunction "1_1") (pintype "passive"))
    )
    (net (code "87") (name "Net-(L2-Pad2)") (class "Default")
      (node (ref "L2") (pin "2") (pinfunction "2_2") (pintype "passive"))
      (node (ref "X2") (pin "D+") (pinfunction "D+_D+") (pintype "bidirectional"))
    )
    (net (code "88") (name "Net-(L2-Pad3)") (class "Default")
      (node (ref "L2") (pin "3") (pinfunction "3_3") (pintype "passive"))
      (node (ref "X2") (pin "D-") (pinfunction "D-_D-") (pintype "bidirectional"))
    )
    (net (code "89") (name "Net-(L2-Pad5)") (class "Default")
      (node (ref "L2") (pin "5") (pinfunction "5_5") (pintype "passive"))
      (node (ref "R97") (pin "1") (pinfunction "1_1") (pintype "passive"))
    )
    (net (code "90") (name "Net-(L2-Pad6)") (class "Default")
      (node (ref "L2") (pin "6") (pinfunction "6_6") (pintype "passive"))
      (node (ref "R96") (pin "1") (pinfunction "1_1") (pintype "passive"))
    )
    (net (code "91") (name "Net-(LED1-Pad1)") (class "Default")
      (node (ref "LED1") (pin "1") (pinfunction "1_1") (pintype "passive"))
      (node (ref "R49") (pin "2") (pinfunction "2_2") (pintype "passive"))
    )
    (net (code "92") (name "Net-(LED1-Pad3)") (class "Default")
      (node (ref "LED1") (pin "3") (pinfunction "3_3") (pintype "passive"))
      (node (ref "R53") (pin "2") (pinfunction "2_2") (pintype "passive"))
    )
    (net (code "93") (name "Net-(LED1-Pad4)") (class "Default")
      (node (ref "LED1") (pin "4") (pinfunction "4_4") (pintype "passive"))
      (node (ref "R52") (pin "2") (pinfunction "2_2") (pintype "passive"))
    )
    (net (code "94") (name "Net-(NTC2-Pad1)") (class "Default")
      (node (ref "NTC2") (pin "1") (pinfunction "1_1") (pintype "passive"))
      (node (ref "R111") (pin "2") (pinfunction "2_2") (pintype "passive"))
      (node (ref "R37") (pin "2") (pinfunction "2_2") (pintype "passive"))
    )
    (net (code "95") (name "Net-(OC1-Pad2)") (class "Default")
      (node (ref "OC1") (pin "2") (pinfunction "2_2") (pintype "passive"))
      (node (ref "R74") (pin "2") (pinfunction "2_2") (pintype "passive"))
    )
    (net (code "96") (name "Net-(Q2-PadG)") (class "Default")
      (node (ref "Q2") (pin "G") (pinfunction "G_G") (pintype "passive"))
      (node (ref "R36") (pin "2") (pinfunction "2_2") (pintype "passive"))
      (node (ref "R38") (pin "1") (pinfunction "1_1") (pintype "passive"))
    )
    (net (code "97") (name "Net-(R2-Pad2)") (class "Default")
      (node (ref "R2") (pin "2") (pinfunction "2_2") (pintype "passive"))
      (node (ref "R3") (pin "2") (pinfunction "2_2") (pintype "passive"))
    )
    (net (code "98") (name "Net-(R3-Pad1)") (class "Default")
      (node (ref "R3") (pin "1") (pinfunction "1_1") (pintype "passive"))
      (node (ref "R4") (pin "1") (pinfunction "1_1") (pintype "passive"))
    )
    (net (code "99") (name "Net-(R7-Pad2)") (class "Default")
      (node (ref "R7") (pin "2") (pinfunction "2_2") (pintype "passive"))
      (node (ref "R8") (pin "1") (pinfunction "1_1") (pintype "passive"))
    )
    (net (code "100") (name "Net-(R10-Pad2)") (class "Default")
      (node (ref "R10") (pin "2") (pinfunction "2_2") (pintype "passive"))
      (node (ref "R9") (pin "1") (pinfunction "1_1") (pintype "passive"))
    )
    (net (code "101") (name "Net-(R11-Pad1)") (class "Default")
      (node (ref "R11") (pin "1") (pinfunction "1_1") (pintype "passive"))
      (node (ref "R12") (pin "1") (pinfunction "1_1") (pintype "passive"))
    )
    (net (code "102") (name "Net-(R27-Pad2)") (class "Default")
      (node (ref "R27") (pin "2") (pinfunction "2_2") (pintype "passive"))
      (node (ref "R30") (pin "1") (pinfunction "1_1") (pintype "passive"))
    )
    (net (code "103") (name "Net-(R30-Pad2)") (class "Default")
      (node (ref "R30") (pin "2") (pinfunction "2_2") (pintype "passive"))
      (node (ref "R33") (pin "1") (pinfunction "1_1") (pintype "passive"))
      (node (ref "R34") (pin "1") (pinfunction "1_1") (pintype "passive"))
    )
    (net (code "104") (name "Net-(R31-Pad2)") (class "Default")
      (node (ref "R31") (pin "2") (pinfunction "2_2") (pintype "passive"))
      (node (ref "R33") (pin "2") (pinfunction "2_2") (pintype "passive"))
      (node (ref "R34") (pin "2") (pinfunction "2_2") (pintype "passive"))
    )
    (net (code "105") (name "Net-(R54-Pad1)") (class "Default")
      (node (ref "R54") (pin "1") (pinfunction "1_1") (pintype "passive"))
      (node (ref "R59") (pin "2") (pinfunction "2_2") (pintype "passive"))
      (node (ref "R61") (pin "1") (pinfunction "1_1") (pintype "passive"))
      (node (ref "T3") (pin "E") (pinfunction "E_E") (pintype "passive"))
    )
    (net (code "106") (name "Net-(R54-Pad2)") (class "Default")
      (node (ref "R54") (pin "2") (pinfunction "2_2") (pintype "passive"))
      (node (ref "R55") (pin "1") (pinfunction "1_1") (pintype "passive"))
      (node (ref "T3") (pin "B") (pinfunction "B_B") (pintype "passive"))
    )
    (net (code "107") (name "Net-(R59-Pad1)") (class "Default")
      (node (ref "R59") (pin "1") (pinfunction "1_1") (pintype "passive"))
      (node (ref "R60") (pin "1") (pinfunction "1_1") (pintype "passive"))
      (node (ref "T3") (pin "C") (pinfunction "C_C") (pintype "passive"))
    )
    (net (code "108") (name "Net-(R63-Pad1)") (class "Default")
      (node (ref "R63") (pin "1") (pinfunction "1_1") (pintype "passive"))
      (node (ref "R64") (pin "2") (pinfunction "2_2") (pintype "passive"))
    )
    (net (code "109") (name "Net-(R78-Pad1)") (class "Default")
      (node (ref "R78") (pin "1") (pinfunction "1_1") (pintype "passive"))
      (node (ref "R79") (pin "2") (pinfunction "2_2") (pintype "passive"))
      (node (ref "T4") (pin "C") (pinfunction "C_C") (pintype "passive"))
    )
    (net (code "110") (name "Net-(R81-Pad1)") (class "Default")
      (node (ref "R81") (pin "1") (pinfunction "1_1") (pintype "passive"))
      (node (ref "T4") (pin "E") (pinfunction "E_E") (pintype "passive"))
    )
    (net (code "111") (name "Net-(R86-Pad1)") (class "Default")
      (node (ref "R86") (pin "1") (pinfunction "1_1") (pintype "passive"))
      (node (ref "R87") (pin "2") (pinfunction "2_2") (pintype "passive"))
      (node (ref "T5") (pin "B") (pinfunction "B_B") (pintype "passive"))
    )
    (net (code "112") (name "Net-(R109-Pad1)") (class "Default")
      (node (ref "R109") (pin "1") (pinfunction "1_1") (pintype "passive"))
      (node (ref "T7") (pin "B") (pinfunction "B_B") (pintype "passive"))
    )
    (net (code "113") (name "Net-(R112-Pad1)") (class "Default")
      (node (ref "R112") (pin "1") (pinfunction "1_1") (pintype "passive"))
      (node (ref "R115") (pin "1") (pinfunction "1_1") (pintype "passive"))
    )
    (net (code "114") (name "Net-(R113-Pad1)") (class "Default")
      (node (ref "R113") (pin "1") (pinfunction "1_1") (pintype "passive"))
      (node (ref "R114") (pin "1") (pinfunction "1_1") (pintype "passive"))
      (node (ref "T9") (pin "B") (pinfunction "B_B") (pintype "passive"))
    )
    (net (code "115") (name "Net-(R115-Pad2)") (class "Default")
      (node (ref "R115") (pin "2") (pinfunction "2_2") (pintype "passive"))
      (node (ref "T10") (pin "C") (pinfunction "C_C") (pintype "passive"))
    )
    (net (code "116") (name "Net-(R122-Pad2)") (class "Default")
      (node (ref "R122") (pin "2") (pinfunction "2_2") (pintype "passive"))
      (node (ref "R123") (pin "2") (pinfunction "2_2") (pintype "passive"))
      (node (ref "T2") (pin "B") (pinfunction "B_B") (pintype "passive"))
    )
    (net (code "117") (name "Net-(R133-Pad1)") (class "Default")
      (node (ref "R133") (pin "1") (pinfunction "1_1") (pintype "passive"))
      (node (ref "R134") (pin "2") (pinfunction "2_2") (pintype "passive"))
    )
    (net (code "118") (name "Net-(RF1-Pad2)") (class "Default")
      (node (ref "RF1") (pin "2") (pinfunction "2_2") (pintype "passive"))
      (node (ref "X2") (pin "VBUS") (pinfunction "VBUS_VBUS") (pintype "bidirectional"))
    )
    (net (code "119") (name "Net-(T1-B)") (class "Default")
      (node (ref "R7") (pin "1") (pinfunction "1_1") (pintype "passive"))
      (node (ref "T1") (pin "1") (pinfunction "B_1") (pintype "passive"))
      (node (ref "T1_X") (pin "B") (pinfunction "B_B") (pintype "passive"))
      (node (ref "Z1") (pin "3") (pinfunction "C_3") (pintype "passive"))
    )
    (net (code "120") (name "Net-(T1-C)") (class "Default")
      (node (ref "C13") (pin "+") (pinfunction "+_+") (pintype "passive"))
      (node (ref "C29") (pin "2") (pinfunction "2_2") (pintype "passive"))
      (node (ref "R13") (pin "1") (pinfunction "1_1") (pintype "passive"))
      (node (ref "R8") (pin "2") (pinfunction "2_2") (pintype "passive"))
      (node (ref "T1") (pin "4") (pinfunction "C_4") (pintype "passive"))
      (node (ref "T1_X") (pin "C") (pinfunction "C_C") (pintype "passive"))
    )
    (net (code "121") (name "Net-(T1-E)") (class "Default")
      (node (ref "C10") (pin "+") (pinfunction "+_+") (pintype "passive"))
      (node (ref "FB1") (pin "1") (pinfunction "1_1") (pintype "passive"))
      (node (ref "T1") (pin "3") (pinfunction "E_3") (pintype "passive"))
      (node (ref "T1_X") (pin "E") (pinfunction "E_E") (pintype "passive"))
    )
    (net (code "122") (name "Net-(TRF1-2-Pad1)") (class "Default")
      (node (ref "TRF1") (pin "1") (pinfunction "2_1") (pintype "passive"))
      (node (ref "TRF1") (pin "17") (pinfunction "3_17") (pintype "passive"))
      (node (ref "TRF1") (pin "18") (pinfunction "2_18") (pintype "passive"))
      (node (ref "TRF1") (pin "2") (pinfunction "3_2") (pintype "passive"))
      (node (ref "TRF1") (pin "36") (pinfunction "3_36") (pintype "passive"))
      (node (ref "TRF1") (pin "37") (pinfunction "2_37") (pintype "passive"))
      (node (ref "TRF1") (pin "53") (pinfunction "3_53") (pintype "passive"))
      (node (ref "TRF1") (pin "54") (pinfunction "2_54") (pintype "passive"))
    )
    (net (code "123") (name "Net-(U1-BOOT0)") (class "Default")
      (node (ref "R56") (pin "2") (pinfunction "2_2") (pintype "passive"))
      (node (ref "U1") (pin "44") (pinfunction "BOOT0_44") (pintype "bidirectional"))
    )
    (net (code "124") (name "Net-(U1-VDDA)") (class "Default")
      (node (ref "C31") (pin "1") (pinfunction "1_1") (pintype "passive"))
      (node (ref "C32") (pin "1") (pinfunction "1_1") (pintype "passive"))
      (node (ref "FB4") (pin "1") (pinfunction "1_1") (pintype "passive"))
      (node (ref "U1") (pin "9") (pinfunction "VDDA_9") (pintype "bidirectional"))
    )
    (net (code "125") (name "Net-(U2-BS)") (class "Default")
      (node (ref "R194") (pin "1") (pinfunction "1_1") (pintype "passive"))
      (node (ref "U2") (pin "1") (pinfunction "BS_1") (pintype "bidirectional"))
    )
    (net (code "126") (name "Net-(U2-EN)") (class "Default")
      (node (ref "R193") (pin "1") (pinfunction "1_1") (pintype "passive"))
      (node (ref "U2") (pin "4") (pinfunction "EN_4") (pintype "bidirectional"))
    )
    (net (code "127") (name "Net-(U2-LX)") (class "Default")
      (node (ref "C77") (pin "2") (pinfunction "2_2") (pintype "passive"))
      (node (ref "D18") (pin "C") (pinfunction "C_C") (pintype "passive"))
      (node (ref "L5") (pin "1") (pinfunction "1_1") (pintype "passive"))
      (node (ref "U2") (pin "6") (pinfunction "LX_6") (pintype "bidirectional"))
    )
    (net (code "128") (name "Net-(X1B-1)") (class "Default")
      (node (ref "NTC1") (pin "P$2") (pinfunction "2_P$2") (pintype "passive"))
      (node (ref "NTC1") (pin "P$3") (pinfunction "2_P$3") (pintype "passive"))
      (node (ref "X1") (pin "2") (pinfunction "1_2") (pintype "passive"))
    )
    (net (code "129") (name "Net-(X3C-1)") (class "Default")
      (node (ref "RL1") (pin "P0") (pinfunction "P0_P0") (pintype "passive"))
      (node (ref "RL1") (pin "P1") (pinfunction "P1_P1") (pintype "passive"))
      (node (ref "X3") (pin "3") (pinfunction "1_3") (pintype "passive"))
    )
    (net (code "130") (name "Net-(X3D-1)") (class "Default")
      (node (ref "RL1") (pin "S0") (pinfunction "S0_S0") (pintype "passive"))
      (node (ref "X3") (pin "4") (pinfunction "1_4") (pintype "passive"))
    )
    (net (code "131") (name "Net-(X4B-1)") (class "Default")
      (node (ref "R94") (pin "1") (pinfunction "1_1") (pintype "passive"))
      (node (ref "X4") (pin "2") (pinfunction "1_2") (pintype "passive"))
    )
    (net (code "132") (name "Net-(X4C-1)") (class "Default")
      (node (ref "D11") (pin "C") (pinfunction "C_C") (pintype "passive"))
      (node (ref "X4") (pin "3") (pinfunction "1_3") (pintype "passive"))
    )
    (net (code "133") (name "Net-(Z3-C)") (class "Default")
      (node (ref "R127") (pin "1") (pinfunction "1_1") (pintype "passive"))
      (node (ref "R95") (pin "1") (pinfunction "1_1") (pintype "passive"))
      (node (ref "R99") (pin "2") (pinfunction "2_2") (pintype "passive"))
      (node (ref "T6") (pin "B") (pinfunction "B_B") (pintype "passive"))
      (node (ref "Z3") (pin "3") (pinfunction "C_3") (pintype "passive"))
    )
    (net (code "134") (name "Net-(Z4-C)") (class "Default")
      (node (ref "R91") (pin "2") (pinfunction "2_2") (pintype "passive"))
      (node (ref "R92") (pin "2") (pinfunction "2_2") (pintype "passive"))
      (node (ref "R93") (pin "2") (pinfunction "2_2") (pintype "passive"))
      (node (ref "Z4") (pin "3") (pinfunction "C_3") (pintype "passive"))
    )
    (net (code "135") (name "Net-(Z5-A)") (class "Default")
      (node (ref "R103") (pin "2") (pinfunction "2_2") (pintype "passive"))
      (node (ref "Z5") (pin "1") (pinfunction "A_1") (pintype "passive"))
    )
    (net (code "136") (name "Net-(Z5-C)") (class "Default")
      (node (ref "OC2") (pin "2") (pinfunction "2_2") (pintype "passive"))
      (node (ref "Z5") (pin "3") (pinfunction "C_3") (pintype "passive"))
    )
    (net (code "137") (name "Net-(Z6-C)") (class "Default")
      (node (ref "R104") (pin "1") (pinfunction "1_1") (pintype "passive"))
      (node (ref "T6") (pin "C") (pinfunction "C_C") (pintype "passive"))
      (node (ref "Z6") (pin "3") (pinfunction "C_3") (pintype "passive"))
    )
    (net (code "138") (name "Net-(Z7-C)") (class "Default")
      (node (ref "D14") (pin "C") (pinfunction "C_C") (pintype "passive"))
      (node (ref "R112") (pin "2") (pinfunction "2_2") (pintype "passive"))
      (node (ref "R113") (pin "2") (pinfunction "2_2") (pintype "passive"))
      (node (ref "Z7") (pin "3") (pinfunction "C_3") (pintype "passive"))
    )
    (net (code "139") (name "OSC1") (class "Default")
      (node (ref "C23") (pin "1") (pinfunction "1_1") (pintype "passive"))
      (node (ref "U1") (pin "5") (pinfunction "PF0/OSC_IN_5") (pintype "bidirectional"))
      (node (ref "Y1") (pin "1") (pinfunction "1_1") (pintype "bidirectional"))
    )
    (net (code "140") (name "OSC2") (class "Default")
      (node (ref "C26") (pin "1") (pinfunction "1_1") (pintype "passive"))
      (node (ref "U1") (pin "6") (pinfunction "PF1/OSC_OUT_6") (pintype "bidirectional"))
      (node (ref "Y1") (pin "4") (pinfunction "4.GND_1_4") (pintype "bidirectional"))
    )
    (net (code "141") (name "OUTPUT_HEALTHY") (class "Default")
      (node (ref "C1") (pin "1") (pinfunction "1_1") (pintype "passive"))
      (node (ref "U1") (pin "2") (pinfunction "PC13_2") (pintype "bidirectional"))
    )
    (net (code "142") (name "OVER_VOLT") (class "Default")
      (node (ref "R95") (pin "2") (pinfunction "2_2") (pintype "passive"))
      (node (ref "U1") (pin "38") (pinfunction "PA15_38") (pintype "bidirectional"))
    )
    (net (code "143") (name "PT100_ADC") (class "Default")
      (node (ref "C70") (pin "2") (pinfunction "2_2") (pintype "passive"))
      (node (ref "D13") (pin "3") (pinfunction "AC_3") (pintype "passive"))
      (node (ref "R108") (pin "2") (pinfunction "2_2") (pintype "passive"))
      (node (ref "U1") (pin "11") (pinfunction "PA1_11") (pintype "bidirectional"))
    )
    (net (code "144") (name "RELAY_OP") (class "Default")
      (node (ref "R86") (pin "2") (pinfunction "2_2") (pintype "passive"))
      (node (ref "U1") (pin "12") (pinfunction "PA2_12") (pintype "bidirectional"))
    )
    (net (code "145") (name "SWCLK") (class "Default")
      (node (ref "PROG1") (pin "2") (pinfunction "PRG_SWCLK_2") (pintype "passive"))
      (node (ref "U1") (pin "37") (pinfunction "PA14_37") (pintype "bidirectional"))
    )
    (net (code "146") (name "SWDIO") (class "Default")
      (node (ref "PROG1") (pin "4") (pinfunction "PRG_SWDIO_4") (pintype "passive"))
      (node (ref "U1") (pin "34") (pinfunction "PA13_34") (pintype "bidirectional"))
    )
    (net (code "147") (name "USB_DM") (class "Default")
      (node (ref "C66") (pin "1") (pinfunction "1_1") (pintype "passive"))
      (node (ref "R97") (pin "2") (pinfunction "2_2") (pintype "passive"))
      (node (ref "U1") (pin "32") (pinfunction "PA11_32") (pintype "bidirectional"))
    )
    (net (code "148") (name "USB_DP") (class "Default")
      (node (ref "C67") (pin "1") (pinfunction "1_1") (pintype "passive"))
      (node (ref "R100") (pin "1") (pinfunction "1_1") (pintype "passive"))
      (node (ref "R96") (pin "2") (pinfunction "2_2") (pintype "passive"))
      (node (ref "U1") (pin "33") (pinfunction "PA12_33") (pintype "bidirectional"))
    )
    (net (code "149") (name "VAUX_DC") (class "Default")
      (node (ref "C110") (pin "2") (pinfunction "2_2") (pintype "passive"))
      (node (ref "C20") (pin "+") (pinfunction "+_+") (pintype "passive"))
      (node (ref "D6") (pin "C") (pinfunction "C_C") (pintype "passive"))
      (node (ref "D7") (pin "C") (pinfunction "C_C") (pintype "passive"))
      (node (ref "R193") (pin "2") (pinfunction "2_2") (pintype "passive"))
      (node (ref "R35") (pin "2") (pinfunction "2_2") (pintype "passive"))
      (node (ref "U2") (pin "5") (pinfunction "VIN_5") (pintype "bidirectional"))
    )
    (net (code "150") (name "VBAT_ADC") (class "Default")
      (node (ref "C44") (pin "1") (pinfunction "1_1") (pintype "passive"))
      (node (ref "R57") (pin "2") (pinfunction "2_2") (pintype "passive"))
      (node (ref "R58") (pin "1") (pinfunction "1_1") (pintype "passive"))
      (node (ref "U1") (pin "13") (pinfunction "PA3_13") (pintype "bidirectional"))
    )
    (net (code "151") (name "VOUT+_ADC") (class "Default")
      (node (ref "C41") (pin "1") (pinfunction "1_1") (pintype "passive"))
      (node (ref "R50") (pin "2") (pinfunction "2_2") (pintype "passive"))
      (node (ref "R51") (pin "1") (pinfunction "1_1") (pintype "passive"))
      (node (ref "U1") (pin "14") (pinfunction "PA4_14") (pintype "bidirectional"))
    )
    (net (code "152") (name "V_NTC_ADC") (class "Default")
      (node (ref "C53") (pin "1") (pinfunction "1_1") (pintype "passive"))
      (node (ref "NTC3") (pin "1") (pinfunction "1_1") (pintype "passive"))
      (node (ref "R72") (pin "1") (pinfunction "1_1") (pintype "passive"))
      (node (ref "U1") (pin "10") (pinfunction "PA0_10") (pintype "bidirectional"))
    )
    (net (code "153") (name "V_PWM") (class "Default")
      (node (ref "R84") (pin "1") (pinfunction "1_1") (pintype "passive"))
      (node (ref "U1") (pin "19") (pinfunction "PB1_19") (pintype "bidirectional"))
    )
    (net (code "154") (name "unconnected-(U1-PA6-Pad16)") (class "Default")
      (node (ref "U1") (pin "16") (pinfunction "PA6_16") (pintype "bidirectional"))
    )
    (net (code "155") (name "unconnected-(U1-PA8-Pad29)") (class "Default")
      (node (ref "U1") (pin "29") (pinfunction "PA8_29") (pintype "bidirectional"))
    )
    (net (code "156") (name "unconnected-(U1-PA9-Pad30)") (class "Default")
      (node (ref "U1") (pin "30") (pinfunction "PA9_30") (pintype "bidirectional"))
    )
    (net (code "157") (name "unconnected-(U1-PA10-Pad31)") (class "Default")
      (node (ref "U1") (pin "31") (pinfunction "PA10_31") (pintype "bidirectional"))
    )
    (net (code "158") (name "unconnected-(U1-PB2-Pad20)") (class "Default")
      (node (ref "U1") (pin "20") (pinfunction "PB2_20") (pintype "bidirectional"))
    )
    (net (code "159") (name "unconnected-(U1-PB7-Pad43)") (class "Default")
      (node (ref "U1") (pin "43") (pinfunction "PB7_43") (pintype "bidirectional"))
    )
    (net (code "160") (name "unconnected-(U1-PB8-Pad45)") (class "Default")
      (node (ref "U1") (pin "45") (pinfunction "PB8_45") (pintype "bidirectional"))
    )
    (net (code "161") (name "unconnected-(U1-PB9-Pad46)") (class "Default")
      (node (ref "U1") (pin "46") (pinfunction "PB9_46") (pintype "bidirectional"))
    )
    (net (code "162") (name "unconnected-(U1-PB10-Pad21)") (class "Default")
      (node (ref "U1") (pin "21") (pinfunction "PB10_21") (pintype "bidirectional"))
    )
    (net (code "163") (name "unconnected-(U1-PB11-Pad22)") (class "Default")
      (node (ref "U1") (pin "22") (pinfunction "PB11_22") (pintype "bidirectional"))
    )
    (net (code "164") (name "unconnected-(U1-PB12-Pad25)") (class "Default")
      (node (ref "U1") (pin "25") (pinfunction "PB12_25") (pintype "bidirectional"))
    )
    (net (code "165") (name "unconnected-(U1-PB13-Pad26)") (class "Default")
      (node (ref "U1") (pin "26") (pinfunction "PB13_26") (pintype "bidirectional"))
    )
    (net (code "166") (name "unconnected-(U1-PB14-Pad27)") (class "Default")
      (node (ref "U1") (pin "27") (pinfunction "PB14_27") (pintype "bidirectional"))
    )
    (net (code "167") (name "unconnected-(U1-PB15-Pad28)") (class "Default")
      (node (ref "U1") (pin "28") (pinfunction "PB15_28") (pintype "bidirectional"))
    )
    (net (code "168") (name "unconnected-(U1-PC14{slash}OSC32_IN-Pad3)") (class "Default")
      (node (ref "U1") (pin "3") (pinfunction "PC14/OSC32_IN_3") (pintype "bidirectional"))
    )
    (net (code "169") (name "unconnected-(U1-PC15{slash}OSC32_OUT-Pad4)") (class "Default")
      (node (ref "U1") (pin "4") (pinfunction "PC15/OSC32_OUT_4") (pintype "bidirectional"))
    )
    (net (code "170") (name "unconnected-(U1-VBAT-Pad1)") (class "Default")
      (node (ref "U1") (pin "1") (pinfunction "VBAT_1") (pintype "bidirectional"))
    )
  )
)
